# USB_HUB_IC.net
KiCad netlist of a schematic drawn in Altium Designer
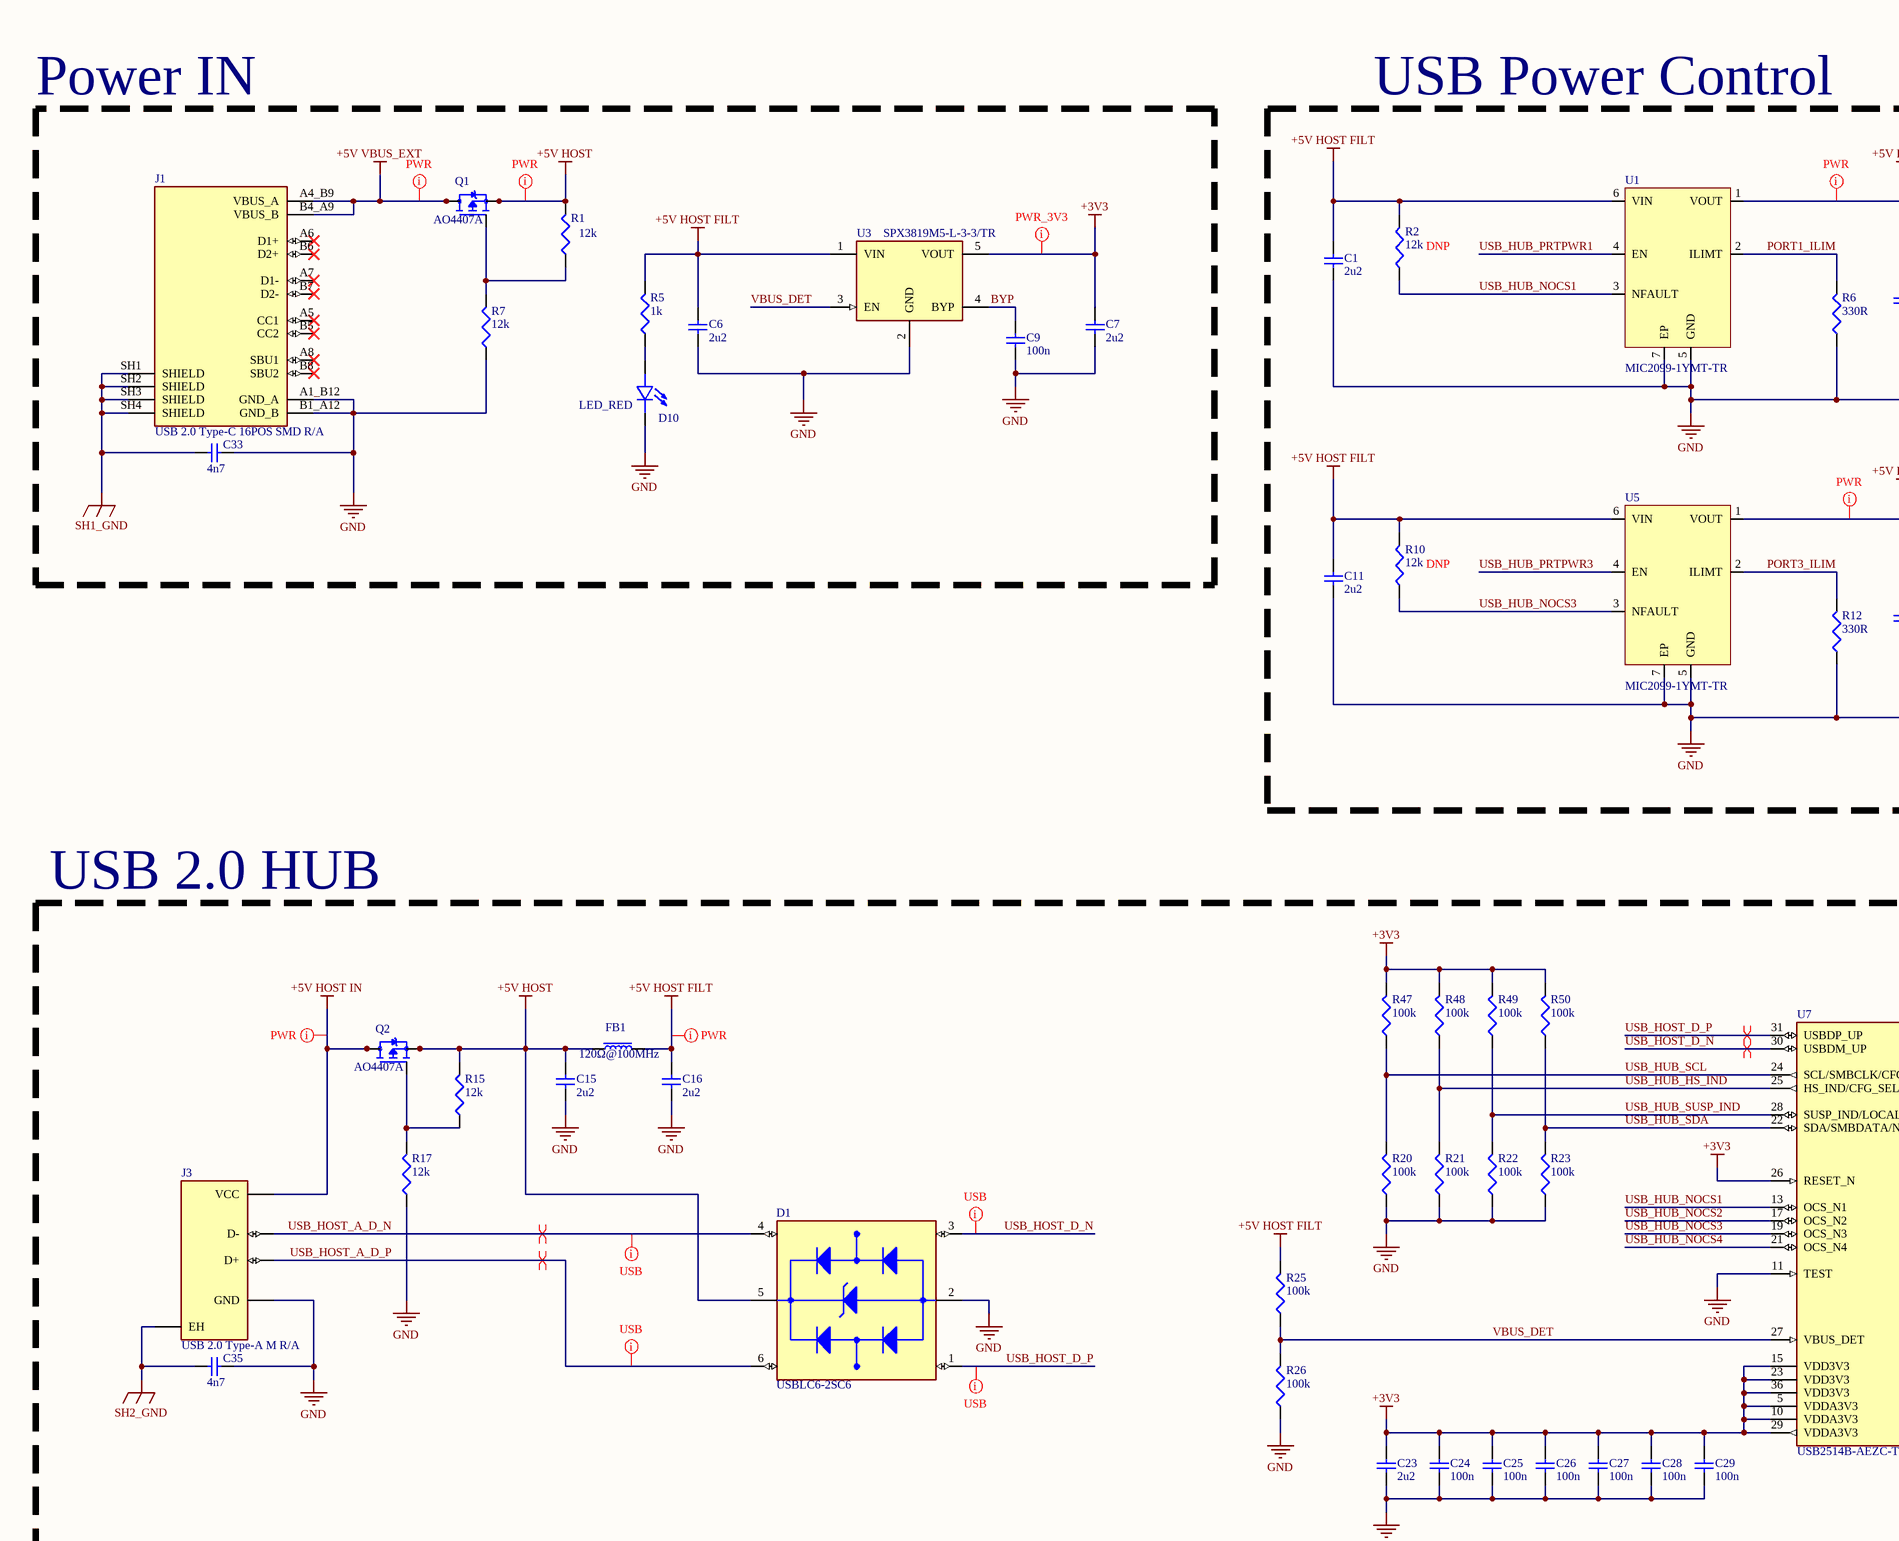
[diagram p0: USB_HUB_IC.SchDoc, top left]
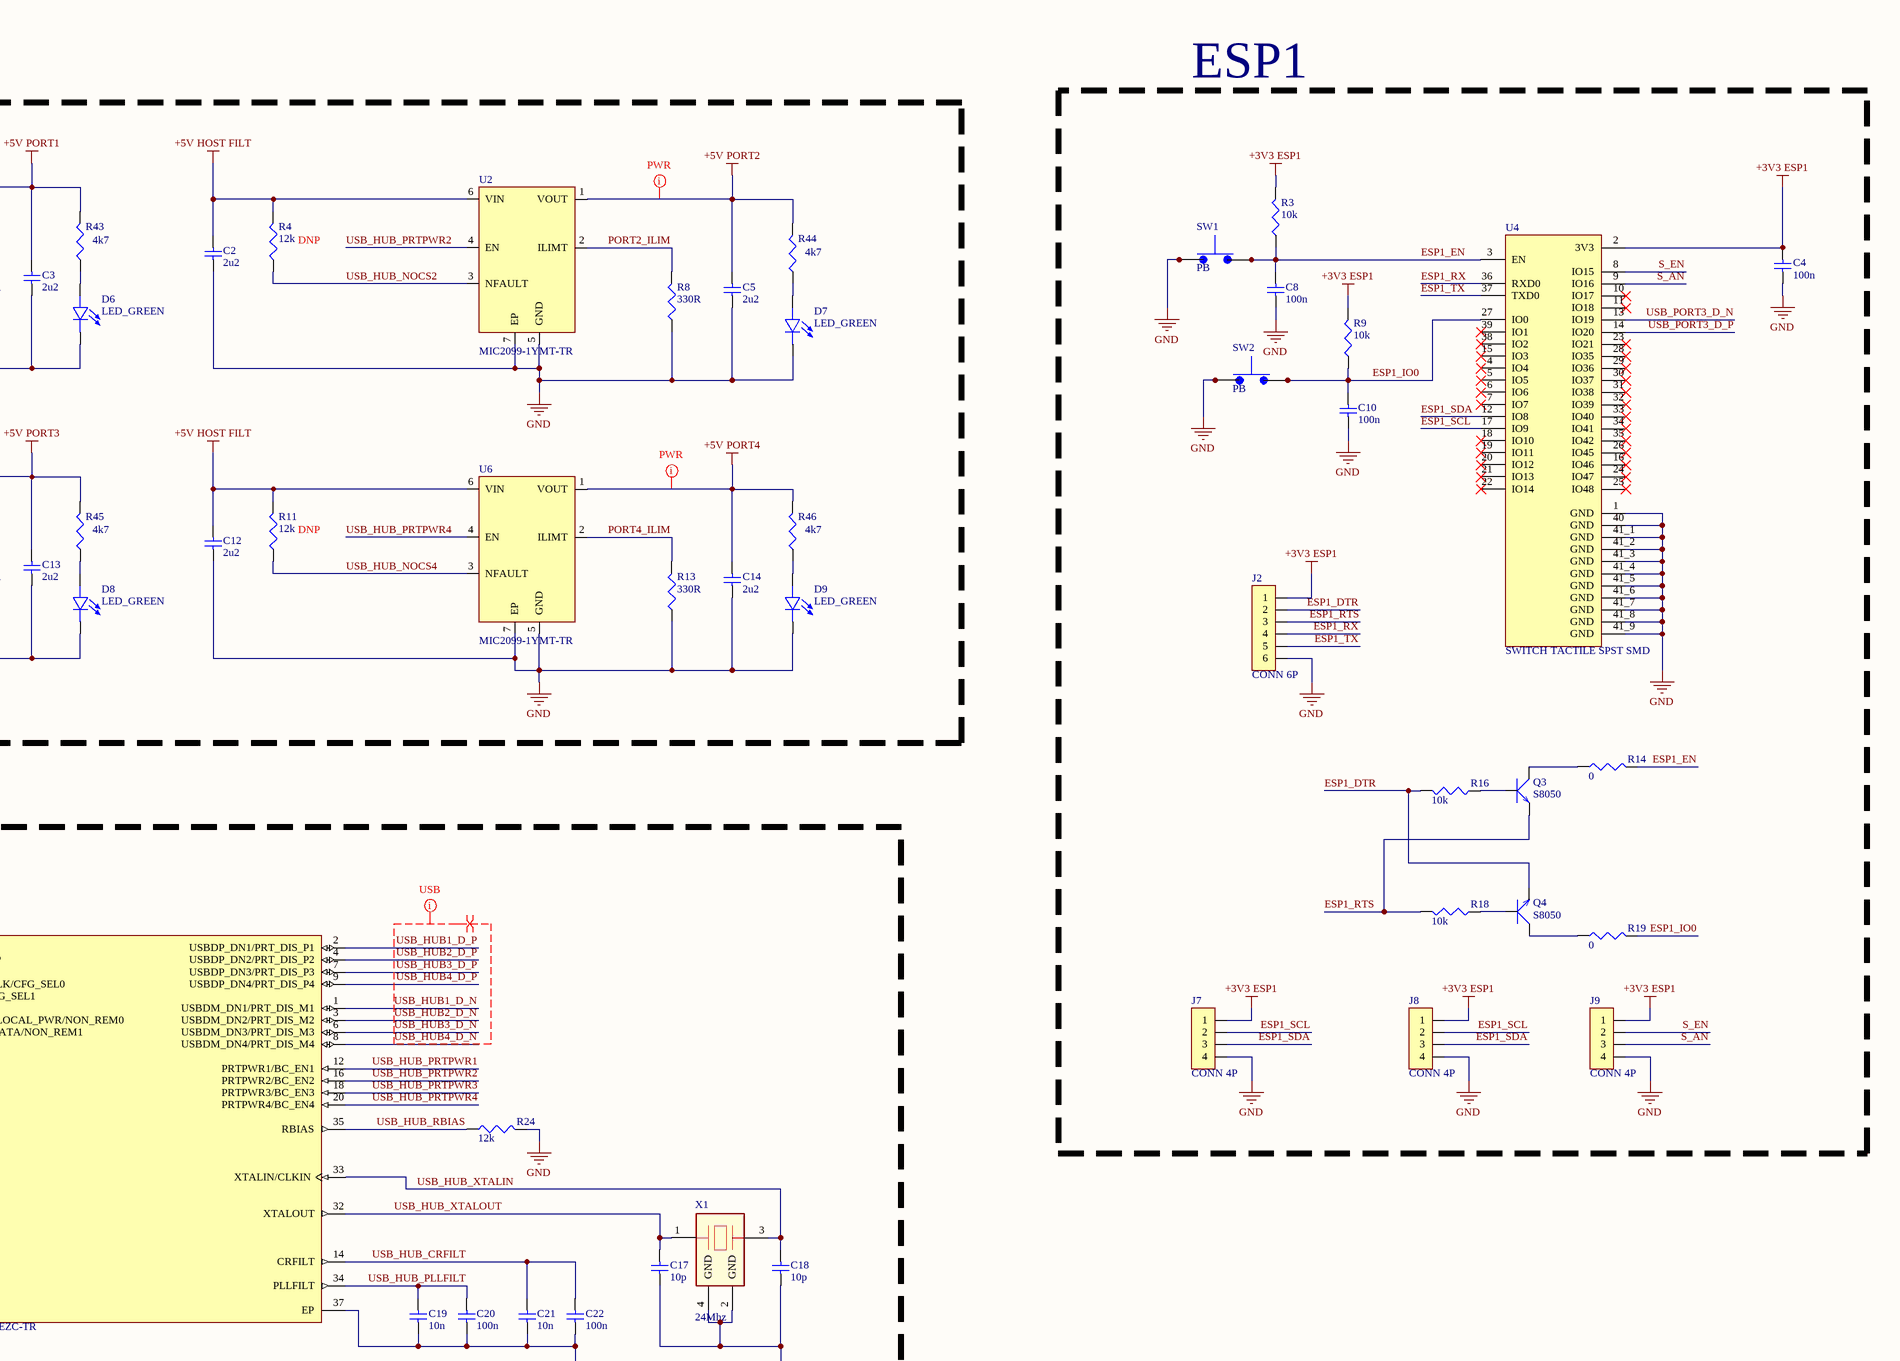
[diagram p1: USB_HUB_IC.SchDoc, top right]
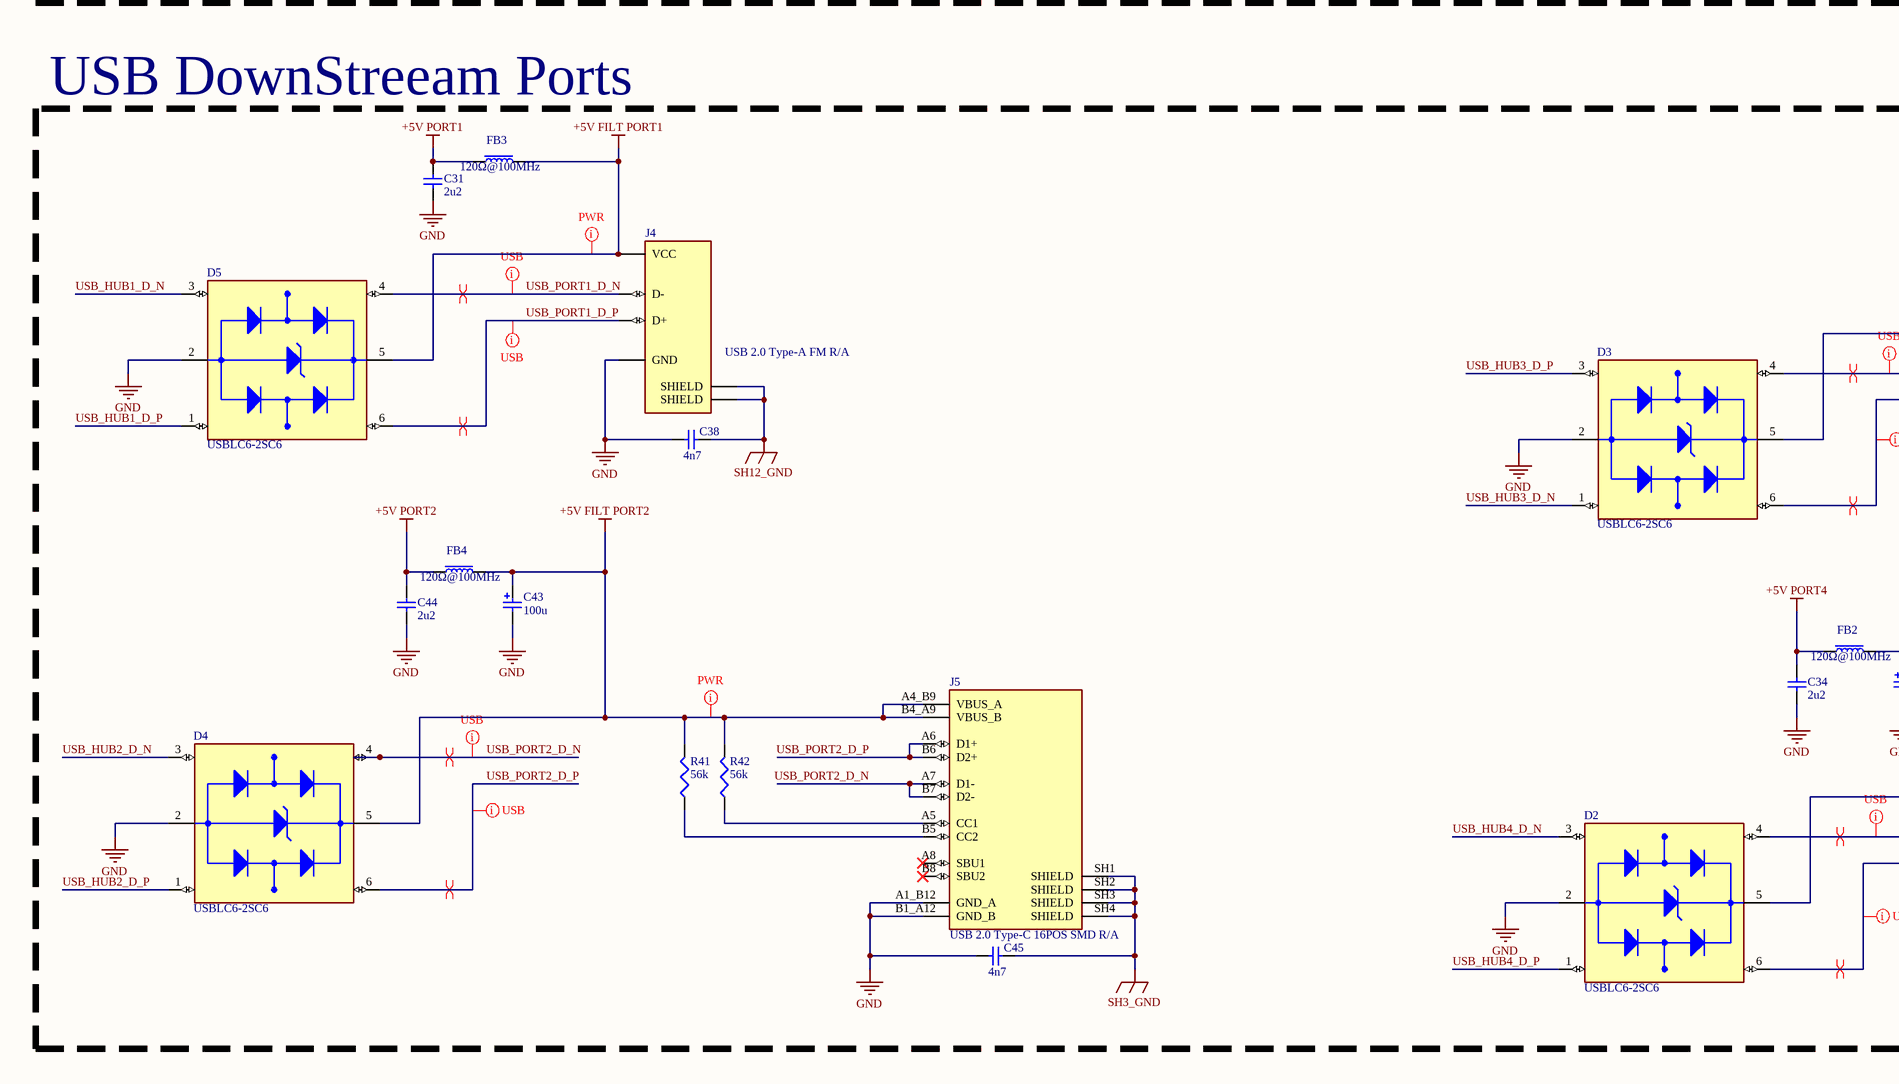
[diagram p2: USB_HUB_IC.SchDoc, bottom left]
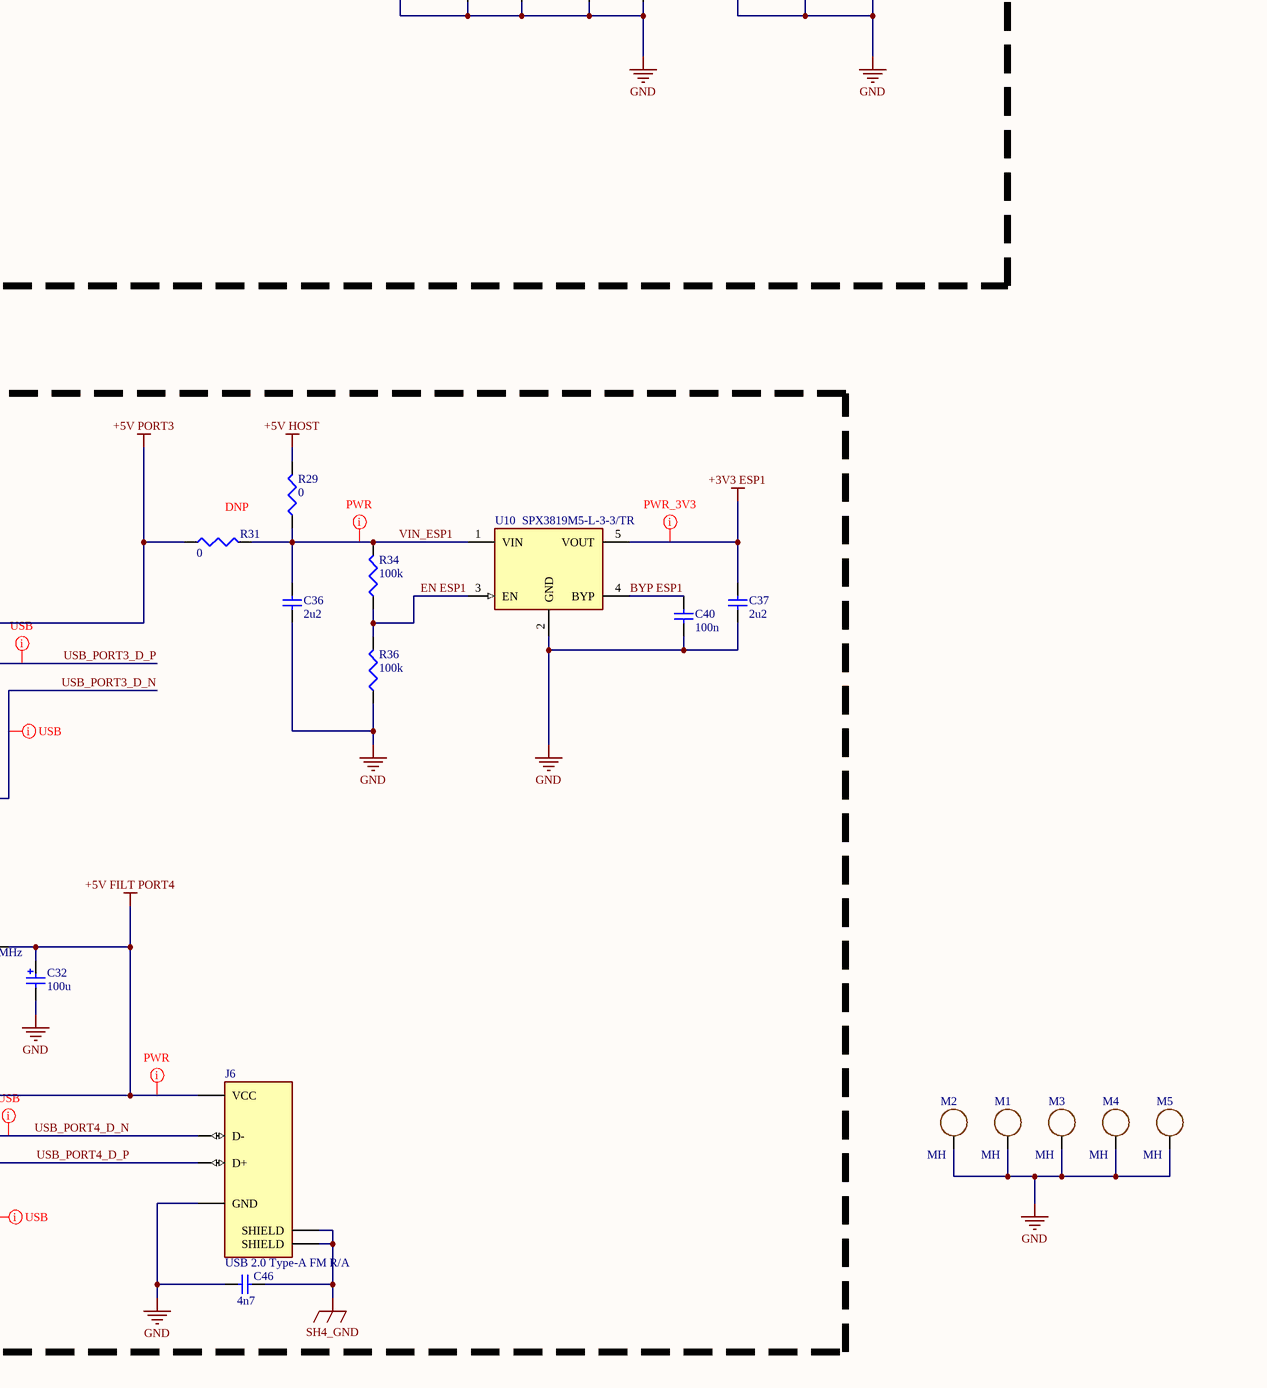
[diagram p3: USB_HUB_IC.SchDoc, bottom right]

(export (version "E")
  (design (tool "Eeschema 10.0.6"))
  (components
    (comp (ref "C1")
      (value "2u2")
      (footprint "CAP_0603")
      (description "CAP CER 2.2uF 16V X7R 0603")
      (fields
        (field (name "MANUFACTURER") "YAGEO")
        (field (name "MANUFACTURER PART NUMBER") "CC0603KRX7R7BB225")
      )
      (libsource (lib "USB2.0_HUB_CAP") (part "YAGEO CC0603KRX7R9BB104_1"))
    )
    (comp (ref "C2")
      (value "2u2")
      (footprint "CAP_0603")
      (description "CAP CER 2.2uF 16V X7R 0603")
      (fields
        (field (name "MANUFACTURER") "YAGEO")
        (field (name "MANUFACTURER PART NUMBER") "CC0603KRX7R7BB225")
      )
      (libsource (lib "USB2.0_HUB_CAP") (part "YAGEO CC0603KRX7R9BB104_1"))
    )
    (comp (ref "C3")
      (value "2u2")
      (footprint "CAP_0603")
      (description "CAP CER 2.2uF 16V X7R 0603")
      (fields
        (field (name "MANUFACTURER") "YAGEO")
        (field (name "MANUFACTURER PART NUMBER") "CC0603KRX7R7BB225")
      )
      (libsource (lib "USB2.0_HUB_CAP") (part "YAGEO CC0603KRX7R9BB104_1"))
    )
    (comp (ref "C4")
      (value "100n")
      (footprint "CAP_0603")
      (description "100nF ±10% 50V Ceramic Capacitor X7R 0603")
      (fields
        (field (name "MANUFACTURER") "YAGEO")
        (field (name "MANUFACTURER PART NUMBER") "CC0603KRX7R9BB104")
      )
      (libsource (lib "USB2.0_HUB_CAP") (part "YAGEO CC0603KRX7R9BB104"))
    )
    (comp (ref "C5")
      (value "2u2")
      (footprint "CAP_0603")
      (description "CAP CER 2.2uF 16V X7R 0603")
      (fields
        (field (name "MANUFACTURER") "YAGEO")
        (field (name "MANUFACTURER PART NUMBER") "CC0603KRX7R7BB225")
      )
      (libsource (lib "USB2.0_HUB_CAP") (part "YAGEO CC0603KRX7R9BB104_1"))
    )
    (comp (ref "C6")
      (value "2u2")
      (footprint "CAP_0603")
      (description "2.2uF ±10% 16V Ceramic Capacitor X7R 0603")
      (fields
        (field (name "MANUFACTURER") "YAGEO")
        (field (name "MANUFACTURER PART NUMBER") "CC0603KRX7R7BB225")
      )
      (libsource (lib "USB2.0_HUB_CAP") (part "YAGEO CC0603KRX7R7BB225"))
    )
    (comp (ref "C7")
      (value "2u2")
      (footprint "CAP_0603")
      (description "2.2uF ±10% 16V Ceramic Capacitor X7R 0603")
      (fields
        (field (name "MANUFACTURER") "YAGEO")
        (field (name "MANUFACTURER PART NUMBER") "CC0603KRX7R7BB225")
      )
      (libsource (lib "USB2.0_HUB_CAP") (part "YAGEO CC0603KRX7R7BB225"))
    )
    (comp (ref "C8")
      (value "100n")
      (footprint "CAP_0603")
      (description "100nF ±10% 50V Ceramic Capacitor X7R 0603")
      (fields
        (field (name "MANUFACTURER") "YAGEO")
        (field (name "MANUFACTURER PART NUMBER") "CC0603KRX7R9BB104")
      )
      (libsource (lib "USB2.0_HUB_CAP") (part "YAGEO CC0603KRX7R9BB104"))
    )
    (comp (ref "C9")
      (value "100n")
      (footprint "CAP_0603")
      (description "100nF ±10% 50V Ceramic Capacitor X7R 0603")
      (fields
        (field (name "MANUFACTURER") "YAGEO")
        (field (name "MANUFACTURER PART NUMBER") "CC0603KRX7R9BB104")
      )
      (libsource (lib "USB2.0_HUB_CAP") (part "YAGEO CC0603KRX7R9BB104"))
    )
    (comp (ref "C10")
      (value "100n")
      (footprint "CAP_0603")
      (description "100nF ±10% 50V Ceramic Capacitor X7R 0603")
      (fields
        (field (name "MANUFACTURER") "YAGEO")
        (field (name "MANUFACTURER PART NUMBER") "CC0603KRX7R9BB104")
      )
      (libsource (lib "USB2.0_HUB_CAP") (part "YAGEO CC0603KRX7R9BB104"))
    )
    (comp (ref "C11")
      (value "2u2")
      (footprint "CAP_0603")
      (description "CAP CER 2.2uF 16V X7R 0603")
      (fields
        (field (name "MANUFACTURER") "YAGEO")
        (field (name "MANUFACTURER PART NUMBER") "CC0603KRX7R7BB225")
      )
      (libsource (lib "USB2.0_HUB_CAP") (part "YAGEO CC0603KRX7R9BB104_1"))
    )
    (comp (ref "C12")
      (value "2u2")
      (footprint "CAP_0603")
      (description "CAP CER 2.2uF 16V X7R 0603")
      (fields
        (field (name "MANUFACTURER") "YAGEO")
        (field (name "MANUFACTURER PART NUMBER") "CC0603KRX7R7BB225")
      )
      (libsource (lib "USB2.0_HUB_CAP") (part "YAGEO CC0603KRX7R9BB104_1"))
    )
    (comp (ref "C13")
      (value "2u2")
      (footprint "CAP_0603")
      (description "CAP CER 2.2uF 16V X7R 0603")
      (fields
        (field (name "MANUFACTURER") "YAGEO")
        (field (name "MANUFACTURER PART NUMBER") "CC0603KRX7R7BB225")
      )
      (libsource (lib "USB2.0_HUB_CAP") (part "YAGEO CC0603KRX7R9BB104_1"))
    )
    (comp (ref "C14")
      (value "2u2")
      (footprint "CAP_0603")
      (description "CAP CER 2.2uF 16V X7R 0603")
      (fields
        (field (name "MANUFACTURER") "YAGEO")
        (field (name "MANUFACTURER PART NUMBER") "CC0603KRX7R7BB225")
      )
      (libsource (lib "USB2.0_HUB_CAP") (part "YAGEO CC0603KRX7R9BB104_1"))
    )
    (comp (ref "C15")
      (value "2u2")
      (footprint "CAP_0603")
      (description "CAP CER 2.2uF 16V X7R 0603")
      (fields
        (field (name "MANUFACTURER") "YAGEO")
        (field (name "MANUFACTURER PART NUMBER") "CC0603KRX7R7BB225")
      )
      (libsource (lib "USB2.0_HUB_CAP") (part "YAGEO CC0603KRX7R9BB104_1"))
    )
    (comp (ref "C16")
      (value "2u2")
      (footprint "CAP_0603")
      (description "CAP CER 2.2uF 16V X7R 0603")
      (fields
        (field (name "MANUFACTURER") "YAGEO")
        (field (name "MANUFACTURER PART NUMBER") "CC0603KRX7R7BB225")
      )
      (libsource (lib "USB2.0_HUB_CAP") (part "YAGEO CC0603KRX7R9BB104_1"))
    )
    (comp (ref "C17")
      (value "10p")
      (footprint "CAP_0603")
      (description "10pF ±1% 50V Ceramic Capacitor NP0 0603")
      (fields
        (field (name "MANUFACTURER") "YAGEO")
        (field (name "MANUFACTURER PART NUMBER") "CC0603FRNPO9BN100")
      )
      (libsource (lib "USB2.0_HUB_CAP") (part "YAGEO CC0603FRNPO9BN100"))
    )
    (comp (ref "C18")
      (value "10p")
      (footprint "CAP_0603")
      (description "10pF ±1% 50V Ceramic Capacitor NP0 0603")
      (fields
        (field (name "MANUFACTURER") "YAGEO")
        (field (name "MANUFACTURER PART NUMBER") "CC0603FRNPO9BN100")
      )
      (libsource (lib "USB2.0_HUB_CAP") (part "YAGEO CC0603FRNPO9BN100"))
    )
    (comp (ref "C19")
      (value "10n")
      (footprint "CAP_0603")
      (description "10nF ±10% 50V Ceramic Capacitor X7R 0603")
      (fields
        (field (name "MANUFACTURER") "YAGEO")
        (field (name "MANUFACTURER PART NUMBER") "CC0603KRX7R9BB103")
      )
      (libsource (lib "USB2.0_HUB_CAP") (part "YAGEO CC0603KRX7R9BB103"))
    )
    (comp (ref "C20")
      (value "100n")
      (footprint "CAP_0603")
      (description "100nF ±10% 50V Ceramic Capacitor X7R 0603")
      (fields
        (field (name "MANUFACTURER") "YAGEO")
        (field (name "MANUFACTURER PART NUMBER") "CC0603KRX7R9BB104")
      )
      (libsource (lib "USB2.0_HUB_CAP") (part "YAGEO CC0603KRX7R9BB104"))
    )
    (comp (ref "C21")
      (value "10n")
      (footprint "CAP_0603")
      (description "10nF ±10% 50V Ceramic Capacitor X7R 0603")
      (fields
        (field (name "MANUFACTURER") "YAGEO")
        (field (name "MANUFACTURER PART NUMBER") "CC0603KRX7R9BB103")
      )
      (libsource (lib "USB2.0_HUB_CAP") (part "YAGEO CC0603KRX7R9BB103"))
    )
    (comp (ref "C22")
      (value "100n")
      (footprint "CAP_0603")
      (description "100nF ±10% 50V Ceramic Capacitor X7R 0603")
      (fields
        (field (name "MANUFACTURER") "YAGEO")
        (field (name "MANUFACTURER PART NUMBER") "CC0603KRX7R9BB104")
      )
      (libsource (lib "USB2.0_HUB_CAP") (part "YAGEO CC0603KRX7R9BB104"))
    )
    (comp (ref "C23")
      (value "2u2")
      (footprint "CAP_0603")
      (description "CAP CER 2.2uF 16V X7R 0603")
      (fields
        (field (name "MANUFACTURER") "YAGEO")
        (field (name "MANUFACTURER PART NUMBER") "CC0603KRX7R7BB225")
      )
      (libsource (lib "USB2.0_HUB_CAP") (part "YAGEO CC0603KRX7R9BB104_1"))
    )
    (comp (ref "C24")
      (value "100n")
      (footprint "CAP_0603")
      (description "100nF ±10% 50V Ceramic Capacitor X7R 0603")
      (fields
        (field (name "MANUFACTURER") "YAGEO")
        (field (name "MANUFACTURER PART NUMBER") "CC0603KRX7R9BB104")
      )
      (libsource (lib "USB2.0_HUB_CAP") (part "YAGEO CC0603KRX7R9BB104"))
    )
    (comp (ref "C25")
      (value "100n")
      (footprint "CAP_0603")
      (description "100nF ±10% 50V Ceramic Capacitor X7R 0603")
      (fields
        (field (name "MANUFACTURER") "YAGEO")
        (field (name "MANUFACTURER PART NUMBER") "CC0603KRX7R9BB104")
      )
      (libsource (lib "USB2.0_HUB_CAP") (part "YAGEO CC0603KRX7R9BB104"))
    )
    (comp (ref "C26")
      (value "100n")
      (footprint "CAP_0603")
      (description "100nF ±10% 50V Ceramic Capacitor X7R 0603")
      (fields
        (field (name "MANUFACTURER") "YAGEO")
        (field (name "MANUFACTURER PART NUMBER") "CC0603KRX7R9BB104")
      )
      (libsource (lib "USB2.0_HUB_CAP") (part "YAGEO CC0603KRX7R9BB104"))
    )
    (comp (ref "C27")
      (value "100n")
      (footprint "CAP_0603")
      (description "100nF ±10% 50V Ceramic Capacitor X7R 0603")
      (fields
        (field (name "MANUFACTURER") "YAGEO")
        (field (name "MANUFACTURER PART NUMBER") "CC0603KRX7R9BB104")
      )
      (libsource (lib "USB2.0_HUB_CAP") (part "YAGEO CC0603KRX7R9BB104"))
    )
    (comp (ref "C28")
      (value "100n")
      (footprint "CAP_0603")
      (description "100nF ±10% 50V Ceramic Capacitor X7R 0603")
      (fields
        (field (name "MANUFACTURER") "YAGEO")
        (field (name "MANUFACTURER PART NUMBER") "CC0603KRX7R9BB104")
      )
      (libsource (lib "USB2.0_HUB_CAP") (part "YAGEO CC0603KRX7R9BB104"))
    )
    (comp (ref "C29")
      (value "100n")
      (footprint "CAP_0603")
      (description "100nF ±10% 50V Ceramic Capacitor X7R 0603")
      (fields
        (field (name "MANUFACTURER") "YAGEO")
        (field (name "MANUFACTURER PART NUMBER") "CC0603KRX7R9BB104")
      )
      (libsource (lib "USB2.0_HUB_CAP") (part "YAGEO CC0603KRX7R9BB104"))
    )
    (comp (ref "C31")
      (value "2u2")
      (footprint "CAP_0603")
      (description "CAP CER 2.2uF 16V X7R 0603")
      (fields
        (field (name "MANUFACTURER") "YAGEO")
        (field (name "MANUFACTURER PART NUMBER") "CC0603KRX7R7BB225")
      )
      (libsource (lib "USB2.0_HUB_CAP") (part "YAGEO CC0603KRX7R9BB104_1"))
    )
    (comp (ref "C32")
      (value "100u")
      (footprint "CAP_SMD")
      (description "100uF ±20% 16V Aluminum Electrolytic Capacitors 2000hrs@105℃")
      (fields
        (field (name "MANUFACTURER") "PANASONIC")
        (field (name "MANUFACTURER PART NUMBER") "EEEFT1C101AR")
      )
      (libsource (lib "USB2.0_HUB_CAP") (part "CAP ALUM 100uF"))
    )
    (comp (ref "C33")
      (value "4n7")
      (footprint "CAP_0603")
      (description "4.7nF ±5% 50V Ceramic Capacitor X7R 0603")
      (fields
        (field (name "MANUFACTURER") "YAGEO")
        (field (name "MANUFACTURER PART NUMBER") "CC0603JRX7R9BB472")
      )
      (libsource (lib "USB2.0_HUB_CAP") (part "YAGEO CC0603JRX7R9BB472"))
    )
    (comp (ref "C34")
      (value "2u2")
      (footprint "CAP_0603")
      (description "CAP CER 2.2uF 16V X7R 0603")
      (fields
        (field (name "MANUFACTURER") "YAGEO")
        (field (name "MANUFACTURER PART NUMBER") "CC0603KRX7R7BB225")
      )
      (libsource (lib "USB2.0_HUB_CAP") (part "YAGEO CC0603KRX7R9BB104_1"))
    )
    (comp (ref "C35")
      (value "4n7")
      (footprint "CAP_0603")
      (description "4.7nF ±5% 50V Ceramic Capacitor X7R 0603")
      (fields
        (field (name "MANUFACTURER") "YAGEO")
        (field (name "MANUFACTURER PART NUMBER") "CC0603JRX7R9BB472")
      )
      (libsource (lib "USB2.0_HUB_CAP") (part "YAGEO CC0603JRX7R9BB472"))
    )
    (comp (ref "C36")
      (value "2u2")
      (footprint "CAP_0603")
      (description "2.2uF ±10% 16V Ceramic Capacitor X7R 0603")
      (fields
        (field (name "MANUFACTURER") "YAGEO")
        (field (name "MANUFACTURER PART NUMBER") "CC0603KRX7R7BB225")
      )
      (libsource (lib "USB2.0_HUB_CAP") (part "YAGEO CC0603KRX7R7BB225"))
    )
    (comp (ref "C37")
      (value "2u2")
      (footprint "CAP_0603")
      (description "2.2uF ±10% 16V Ceramic Capacitor X7R 0603")
      (fields
        (field (name "MANUFACTURER") "YAGEO")
        (field (name "MANUFACTURER PART NUMBER") "CC0603KRX7R7BB225")
      )
      (libsource (lib "USB2.0_HUB_CAP") (part "YAGEO CC0603KRX7R7BB225"))
    )
    (comp (ref "C38")
      (value "4n7")
      (footprint "CAP_0603")
      (description "4.7nF ±5% 50V Ceramic Capacitor X7R 0603")
      (fields
        (field (name "MANUFACTURER") "YAGEO")
        (field (name "MANUFACTURER PART NUMBER") "CC0603JRX7R9BB472")
      )
      (libsource (lib "USB2.0_HUB_CAP") (part "YAGEO CC0603JRX7R9BB472"))
    )
    (comp (ref "C40")
      (value "100n")
      (footprint "CAP_0603")
      (description "100nF ±10% 50V Ceramic Capacitor X7R 0603")
      (fields
        (field (name "MANUFACTURER") "YAGEO")
        (field (name "MANUFACTURER PART NUMBER") "CC0603KRX7R9BB104")
      )
      (libsource (lib "USB2.0_HUB_CAP") (part "YAGEO CC0603KRX7R9BB104"))
    )
    (comp (ref "C43")
      (value "100u")
      (footprint "CAP_SMD")
      (description "100uF ±20% 16V Aluminum Electrolytic Capacitors 2000hrs@105℃")
      (fields
        (field (name "MANUFACTURER") "PANASONIC")
        (field (name "MANUFACTURER PART NUMBER") "EEEFT1C101AR")
      )
      (libsource (lib "USB2.0_HUB_CAP") (part "CAP ALUM 100uF"))
    )
    (comp (ref "C44")
      (value "2u2")
      (footprint "CAP_0603")
      (description "CAP CER 2.2uF 16V X7R 0603")
      (fields
        (field (name "MANUFACTURER") "YAGEO")
        (field (name "MANUFACTURER PART NUMBER") "CC0603KRX7R7BB225")
      )
      (libsource (lib "USB2.0_HUB_CAP") (part "YAGEO CC0603KRX7R9BB104_1"))
    )
    (comp (ref "C45")
      (value "4n7")
      (footprint "CAP_0603")
      (description "4.7nF ±5% 50V Ceramic Capacitor X7R 0603")
      (fields
        (field (name "MANUFACTURER") "YAGEO")
        (field (name "MANUFACTURER PART NUMBER") "CC0603JRX7R9BB472")
      )
      (libsource (lib "USB2.0_HUB_CAP") (part "YAGEO CC0603JRX7R9BB472"))
    )
    (comp (ref "C46")
      (value "4n7")
      (footprint "CAP_0603")
      (description "4.7nF ±5% 50V Ceramic Capacitor X7R 0603")
      (fields
        (field (name "MANUFACTURER") "YAGEO")
        (field (name "MANUFACTURER PART NUMBER") "CC0603JRX7R9BB472")
      )
      (libsource (lib "USB2.0_HUB_CAP") (part "YAGEO CC0603JRX7R9BB472"))
    )
    (comp (ref "D1")
      (value "USBLC6-2SC6")
      (footprint "USBLC6-2SC6_SOT-23-6L")
      (description "17VC Clamp 5A Ipp ESD DIODE SOT-23-6L")
      (fields (field (name "MANUFACTURER") "ST") (field (name "LCSC PART NUMBER") "C7519"))
      (libsource (lib "USB2.0_HUB_Diode") (part "ST USBLC6-2SC6"))
    )
    (comp (ref "D2")
      (value "USBLC6-2SC6")
      (footprint "USBLC6-2SC6_SOT-23-6L")
      (description "17VC Clamp 5A Ipp ESD DIODE SOT-23-6L")
      (fields (field (name "MANUFACTURER") "ST") (field (name "LCSC PART NUMBER") "C7519"))
      (libsource (lib "USB2.0_HUB_Diode") (part "ST USBLC6-2SC6"))
    )
    (comp (ref "D3")
      (value "USBLC6-2SC6")
      (footprint "USBLC6-2SC6_SOT-23-6L")
      (description "17VC Clamp 5A Ipp ESD DIODE SOT-23-6L")
      (fields (field (name "MANUFACTURER") "ST") (field (name "LCSC PART NUMBER") "C7519"))
      (libsource (lib "USB2.0_HUB_Diode") (part "ST USBLC6-2SC6"))
    )
    (comp (ref "D4")
      (value "USBLC6-2SC6")
      (footprint "USBLC6-2SC6_SOT-23-6L")
      (description "17VC Clamp 5A Ipp ESD DIODE SOT-23-6L")
      (fields (field (name "MANUFACTURER") "ST") (field (name "LCSC PART NUMBER") "C7519"))
      (libsource (lib "USB2.0_HUB_Diode") (part "ST USBLC6-2SC6"))
    )
    (comp (ref "D5")
      (value "USBLC6-2SC6")
      (footprint "USBLC6-2SC6_SOT-23-6L")
      (description "17VC Clamp 5A Ipp ESD DIODE SOT-23-6L")
      (fields (field (name "MANUFACTURER") "ST") (field (name "LCSC PART NUMBER") "C7519"))
      (libsource (lib "USB2.0_HUB_Diode") (part "ST USBLC6-2SC6"))
    )
    (comp (ref "D6")
      (value "LED_GREEN")
      (footprint "LED_0805")
      (description "Green 535nm LED Indication - Discrete 2.6V~3.2V 0805")
      (fields
        (field (name "MANUFACTURER") "TONYU")
        (field (name "MANUFACTURER PART NUMBER") "DY-S2012508UGC-T5-3T-03")
      )
      (libsource (lib "USB2.0_HUB_Diode") (part "LED_GREEN"))
    )
    (comp (ref "D7")
      (value "LED_GREEN")
      (footprint "LED_0805")
      (description "Green 535nm LED Indication - Discrete 2.6V~3.2V 0805")
      (fields
        (field (name "MANUFACTURER") "TONYU")
        (field (name "MANUFACTURER PART NUMBER") "DY-S2012508UGC-T5-3T-03")
      )
      (libsource (lib "USB2.0_HUB_Diode") (part "LED_GREEN"))
    )
    (comp (ref "D8")
      (value "LED_GREEN")
      (footprint "LED_0805")
      (description "Green 535nm LED Indication - Discrete 2.6V~3.2V 0805")
      (fields
        (field (name "MANUFACTURER") "TONYU")
        (field (name "MANUFACTURER PART NUMBER") "DY-S2012508UGC-T5-3T-03")
      )
      (libsource (lib "USB2.0_HUB_Diode") (part "LED_GREEN"))
    )
    (comp (ref "D9")
      (value "LED_GREEN")
      (footprint "LED_0805")
      (description "Green 535nm LED Indication - Discrete 2.6V~3.2V 0805")
      (fields
        (field (name "MANUFACTURER") "TONYU")
        (field (name "MANUFACTURER PART NUMBER") "DY-S2012508UGC-T5-3T-03")
      )
      (libsource (lib "USB2.0_HUB_Diode") (part "LED_GREEN"))
    )
    (comp (ref "D10")
      (value "LED_RED")
      (footprint "LED_0805")
      (description "LED RED WATER CLEAR 0805 SMD")
      (fields
        (field (name "MANUFACTURER") "Guiguang light")
        (field (name "MANUFACTURER PART NUMBER") "GL0805UR01")
      )
      (libsource (lib "USB2.0_HUB_Diode") (part "LED_RED"))
    )
    (comp (ref "FB1")
      (value "120Ω@100MHz")
      (footprint "FB_0805")
      (description "FERRITE BEAD 120Ω 0805 1LN")
      (fields
        (field (name "MANUFACTURER") "muRata")
        (field (name "MANUFACTURER PART NUMBER") "BLM21PG121SN1D")
      )
      (libsource (lib "USB2.0_HUB_FB") (part "muRata BLM21PG121SN1D"))
    )
    (comp (ref "FB2")
      (value "120Ω@100MHz")
      (footprint "FB_0805")
      (description "FERRITE BEAD 120Ω 0805 1LN")
      (fields
        (field (name "MANUFACTURER") "muRata")
        (field (name "MANUFACTURER PART NUMBER") "BLM21PG121SN1D")
      )
      (libsource (lib "USB2.0_HUB_FB") (part "muRata BLM21PG121SN1D"))
    )
    (comp (ref "FB3")
      (value "120Ω@100MHz")
      (footprint "FB_0805")
      (description "FERRITE BEAD 120Ω 0805 1LN")
      (fields
        (field (name "MANUFACTURER") "muRata")
        (field (name "MANUFACTURER PART NUMBER") "BLM21PG121SN1D")
      )
      (libsource (lib "USB2.0_HUB_FB") (part "muRata BLM21PG121SN1D"))
    )
    (comp (ref "FB4")
      (value "120Ω@100MHz")
      (footprint "FB_0805")
      (description "FERRITE BEAD 120Ω 0805 1LN")
      (fields
        (field (name "MANUFACTURER") "muRata")
        (field (name "MANUFACTURER PART NUMBER") "BLM21PG121SN1D")
      )
      (libsource (lib "USB2.0_HUB_FB") (part "muRata BLM21PG121SN1D"))
    )
    (comp (ref "J1")
      (value "USB 2.0 Type-C 16POS SMD R/A")
      (footprint "GT-USB-7010B")
      (description "USB-C (USB TYPE-C) Receptacle Connector 16 Position Surface Mount, Right Angle")
      (fields
        (field (name "MANUFACTURER") "G-Switch")
        (field (name "MANUFACTURER PART NUMBER") "GT-USB-7010ASV")
      )
      (libsource (lib "USB2.0_HUB_CONN") (part "GT-USB-7010B"))
    )
    (comp (ref "J2")
      (value "CONN 6P")
      (footprint "JST_6P_GH_W/A")
      (description "Connector Header 6 position 1.25mm Pitch 1A Surface Mount, Right Angle -25℃~+85℃")
      (fields
        (field (name "MANUFACTURER") "SHOU HAN")
        (field (name "MANUFACTURER PART NUMBER") "1.25-6PWTDK")
      )
      (libsource (lib "USB2.0_HUB_CONN") (part "JST_6P_GH_R/A"))
    )
    (comp (ref "J3")
      (value "USB 2.0 Type-A M R/A")
      (footprint "Male USB 2.0 Type-A 4POS SMD R/A")
      (description "USB-A (USB TYPE-A) Receptacle Connector 4 Position Surface Mount, Right Angle")
      (fields (field (name "MANUFACTURER") "XUNPU") (field (name "MANUFACTURER PART NUMBER") "USB-212-BCW"))
      (libsource (lib "USB2.0_HUB_CONN") (part "USB 2.0 Type-A M R/A"))
    )
    (comp (ref "J4")
      (value "USB 2.0 Type-A FM R/A")
      (footprint "Femalem USB 2.0 Type-A 4POS SMD R/A")
      (description "USB-A (USB TYPE-A) Receptacle Connector 4 Position Surface Mount, Right Angle")
      (fields
        (field (name "MANUFACTURER") "SHOU HAN")
        (field (name "MANUFACTURER PART NUMBER") "10.0 QHHTZB6.3")
      )
      (libsource (lib "USB2.0_HUB_CONN") (part "USB 2.0 Type-A FM R/A"))
    )
    (comp (ref "J5")
      (value "USB 2.0 Type-C 16POS SMD R/A")
      (footprint "GT-USB-7010B")
      (description "USB-C (USB TYPE-C) Receptacle Connector 16 Position Surface Mount, Right Angle")
      (fields
        (field (name "MANUFACTURER") "G-Switch")
        (field (name "MANUFACTURER PART NUMBER") "GT-USB-7010ASV")
      )
      (libsource (lib "") (part "GT-USB-7010B_1"))
    )
    (comp (ref "J6")
      (value "USB 2.0 Type-A FM R/A")
      (footprint "Femalem USB 2.0 Type-A 4POS SMD R/A")
      (description "USB-A (USB TYPE-A) Receptacle Connector 4 Position Surface Mount, Right Angle")
      (fields
        (field (name "MANUFACTURER") "SHOU HAN")
        (field (name "MANUFACTURER PART NUMBER") "10.0 QHHTZB6.3")
      )
      (libsource (lib "USB2.0_HUB_CONN") (part "USB 2.0 Type-A FM R/A"))
    )
    (comp (ref "J7")
      (value "CONN 4P")
      (footprint "JST_4P_GH_R/A")
      (description "Connector Header 4 position 1.25mm Pitch 1A Surface Mount, Right Angle -25℃~+85℃")
      (fields
        (field (name "MANUFACTURER") "XUNPU")
        (field (name "MANUFACTURER PART NUMBER") "WAFER-GH1.25-4PWB")
      )
      (libsource (lib "USB2.0_HUB_CONN") (part "JST_4P_GH_R/A"))
    )
    (comp (ref "J8")
      (value "CONN 4P")
      (footprint "JST_4P_GH_R/A")
      (description "Connector Header 4 position 1.25mm Pitch 1A Surface Mount, Right Angle -25℃~+85℃")
      (fields
        (field (name "MANUFACTURER") "XUNPU")
        (field (name "MANUFACTURER PART NUMBER") "WAFER-GH1.25-4PWB")
      )
      (libsource (lib "USB2.0_HUB_CONN") (part "JST_4P_GH_R/A"))
    )
    (comp (ref "J9")
      (value "CONN 4P")
      (footprint "JST_4P_GH_R/A")
      (description "Connector Header 4 position 1.25mm Pitch 1A Surface Mount, Right Angle -25℃~+85℃")
      (fields
        (field (name "MANUFACTURER") "XUNPU")
        (field (name "MANUFACTURER PART NUMBER") "WAFER-GH1.25-4PWB")
      )
      (libsource (lib "USB2.0_HUB_CONN") (part "JST_4P_GH_R/A"))
    )
    (comp (ref "M1")
      (value "MH")
      (footprint "M2_Mounting_Hole")
      (libsource (lib "USB2.0_HUB") (part "M2_Mounting_hole"))
    )
    (comp (ref "M2")
      (value "MH")
      (footprint "M2_Mounting_Hole")
      (libsource (lib "USB2.0_HUB") (part "M2_Mounting_hole"))
    )
    (comp (ref "M3")
      (value "MH")
      (footprint "M2_Mounting_Hole")
      (libsource (lib "USB2.0_HUB") (part "M2_Mounting_hole"))
    )
    (comp (ref "M4")
      (value "MH")
      (footprint "M2_Mounting_Hole")
      (libsource (lib "USB2.0_HUB") (part "M2_Mounting_hole"))
    )
    (comp (ref "M5")
      (value "MH")
      (footprint "M2_Mounting_Hole")
      (libsource (lib "USB2.0_HUB") (part "M2_Mounting_hole"))
    )
    (comp (ref "Q1")
      (value "AO4407A")
      (footprint "AO4407A_SOIC-8")
      (description "P-Channel 30V 12A 3.1W Surface Mount SOIC-8")
      (fields (field (name "MANUFACTURER") "AOS") (field (name "LCSC PART NUMBER") "C16072"))
      (libsource (lib "USB2.0_HUB") (part "AOS AO4407A"))
    )
    (comp (ref "Q2")
      (value "AO4407A")
      (footprint "AO4407A_SOIC-8")
      (description "P-Channel 30V 12A 3.1W Surface Mount SOIC-8")
      (fields (field (name "MANUFACTURER") "AOS") (field (name "LCSC PART NUMBER") "C16072"))
      (libsource (lib "USB2.0_HUB") (part "AOS AO4407A"))
    )
    (comp (ref "Q3")
      (value "S8050")
      (footprint "S8050_SOT-23")
      (description "Bipolar (BJT) Transistor 25V 500mA 150MHz 300mW Surface Mount SOT-23")
      (fields (field (name "MANUFACTURER") "JSMSEMI") (field (name "LCSC PART NUMBER") "C916390"))
      (libsource (lib "USB2.0_HUB") (part "JSMSEMI S8050"))
    )
    (comp (ref "Q4")
      (value "S8050")
      (footprint "S8050_SOT-23")
      (description "Bipolar (BJT) Transistor 25V 500mA 150MHz 300mW Surface Mount SOT-23")
      (fields (field (name "MANUFACTURER") "JSMSEMI") (field (name "LCSC PART NUMBER") "C916390"))
      (libsource (lib "USB2.0_HUB") (part "JSMSEMI S8050"))
    )
    (comp (ref "R1")
      (value "12k")
      (footprint "RES_0603")
      (description "RES 12kΩ ±1% 100mW 0603")
      (fields
        (field (name "MANUFACTURER") "YAGEO")
        (field (name "MANUFACTURER PART NUMBER") "RC0603FR-0712KL")
      )
      (libsource (lib "USB2.0_HUB_RES") (part "YAGEO RC0603FR-0712KL"))
    )
    (comp (ref "R2")
      (value "12k")
      (footprint "RES_0603")
      (description "RES 12kΩ ±1% 100mW 0603")
      (fields
        (field (name "MANUFACTURER") "YAGEO")
        (field (name "MANUFACTURER PART NUMBER") "RC0603FR-0712KL")
      )
      (libsource (lib "USB2.0_HUB_RES") (part "YAGEO RC0603FR-0712KL"))
    )
    (comp (ref "R3")
      (value "10k")
      (footprint "RES_0603")
      (description "100mW 10kΩ 75V Thick Film Resistor ±100ppm/℃ ±1% 0603 Chip Resistor - Surface Mount RoHS")
      (fields
        (field (name "MANUFACTURER") "YAGEO")
        (field (name "MANUFACTURER PART NUMBER") "RC0603FR-0710KL")
      )
      (libsource (lib "USB2.0_HUB_RES") (part "YAGEO RC0603FR-0710KL"))
    )
    (comp (ref "R4")
      (value "12k")
      (footprint "RES_0603")
      (description "RES 12kΩ ±1% 100mW 0603")
      (fields
        (field (name "MANUFACTURER") "YAGEO")
        (field (name "MANUFACTURER PART NUMBER") "RC0603FR-0712KL")
      )
      (libsource (lib "USB2.0_HUB_RES") (part "YAGEO RC0603FR-0712KL"))
    )
    (comp (ref "R5")
      (value "1k")
      (footprint "RES_0603")
      (description "100mW 1kΩ 75V Thick Film Resistor ±100ppm/℃ ±5% 0603 Chip Resistor - Surface Mount RoHS")
      (fields
        (field (name "MANUFACTURER") "YAGEO")
        (field (name "MANUFACTURER PART NUMBER") "RC0603JR-071KL")
      )
      (libsource (lib "USB2.0_HUB_RES") (part "YAGEO RC0603JR-071KL"))
    )
    (comp (ref "R6")
      (value "330R")
      (footprint "RES_0603")
      (description "RES 330Ω ±5% 100mW 0603")
      (fields
        (field (name "MANUFACTURER") "YAGEO")
        (field (name "MANUFACTURER PART NUMBER") "RC0603JR-07330RL")
      )
      (libsource (lib "USB2.0_HUB_RES") (part "YAGEO RC0603JR-07330RL"))
    )
    (comp (ref "R7")
      (value "12k")
      (footprint "RES_0603")
      (description "RES 12kΩ ±1% 100mW 0603")
      (fields
        (field (name "MANUFACTURER") "YAGEO")
        (field (name "MANUFACTURER PART NUMBER") "RC0603FR-0712KL")
      )
      (libsource (lib "USB2.0_HUB_RES") (part "YAGEO RC0603FR-0712KL"))
    )
    (comp (ref "R8")
      (value "330R")
      (footprint "RES_0603")
      (description "RES 330Ω ±5% 100mW 0603")
      (fields
        (field (name "MANUFACTURER") "YAGEO")
        (field (name "MANUFACTURER PART NUMBER") "RC0603JR-07330RL")
      )
      (libsource (lib "USB2.0_HUB_RES") (part "YAGEO RC0603JR-07330RL"))
    )
    (comp (ref "R9")
      (value "10k")
      (footprint "RES_0603")
      (description "100mW 10kΩ 75V Thick Film Resistor ±100ppm/℃ ±1% 0603 Chip Resistor - Surface Mount RoHS")
      (fields
        (field (name "MANUFACTURER") "YAGEO")
        (field (name "MANUFACTURER PART NUMBER") "RC0603FR-0710KL")
      )
      (libsource (lib "USB2.0_HUB_RES") (part "YAGEO RC0603FR-0710KL"))
    )
    (comp (ref "R10")
      (value "12k")
      (footprint "RES_0603")
      (description "RES 12kΩ ±1% 100mW 0603")
      (fields
        (field (name "MANUFACTURER") "YAGEO")
        (field (name "MANUFACTURER PART NUMBER") "RC0603FR-0712KL")
      )
      (libsource (lib "USB2.0_HUB_RES") (part "YAGEO RC0603FR-0712KL"))
    )
    (comp (ref "R11")
      (value "12k")
      (footprint "RES_0603")
      (description "RES 12kΩ ±1% 100mW 0603")
      (fields
        (field (name "MANUFACTURER") "YAGEO")
        (field (name "MANUFACTURER PART NUMBER") "RC0603FR-0712KL")
      )
      (libsource (lib "USB2.0_HUB_RES") (part "YAGEO RC0603FR-0712KL"))
    )
    (comp (ref "R12")
      (value "330R")
      (footprint "RES_0603")
      (description "RES 330Ω ±5% 100mW 0603")
      (fields
        (field (name "MANUFACTURER") "YAGEO")
        (field (name "MANUFACTURER PART NUMBER") "RC0603JR-07330RL")
      )
      (libsource (lib "USB2.0_HUB_RES") (part "YAGEO RC0603JR-07330RL"))
    )
    (comp (ref "R13")
      (value "330R")
      (footprint "RES_0603")
      (description "RES 330Ω ±5% 100mW 0603")
      (fields
        (field (name "MANUFACTURER") "YAGEO")
        (field (name "MANUFACTURER PART NUMBER") "RC0603JR-07330RL")
      )
      (libsource (lib "USB2.0_HUB_RES") (part "YAGEO RC0603JR-07330RL"))
    )
    (comp (ref "R14")
      (value "0")
      (footprint "RES_0603")
      (description "100mW 0Ω 75V Thick Film Resistor ±5% 0603 Chip Resistor - Surface Mount RoHS")
      (fields
        (field (name "MANUFACTURER") "YAGEO")
        (field (name "MANUFACTURER PART NUMBER") "RC0603JR-070RL")
      )
      (libsource (lib "USB2.0_HUB_RES") (part "YAGEO RC0603JR-070RL"))
    )
    (comp (ref "R15")
      (value "12k")
      (footprint "RES_0603")
      (description "RES 12kΩ ±1% 100mW 0603")
      (fields
        (field (name "MANUFACTURER") "YAGEO")
        (field (name "MANUFACTURER PART NUMBER") "RC0603FR-0712KL")
      )
      (libsource (lib "USB2.0_HUB_RES") (part "YAGEO RC0603FR-0712KL"))
    )
    (comp (ref "R16")
      (value "10k")
      (footprint "RES_0603")
      (description "100mW 10kΩ 75V Thick Film Resistor ±100ppm/℃ ±1% 0603 Chip Resistor - Surface Mount RoHS")
      (fields
        (field (name "MANUFACTURER") "YAGEO")
        (field (name "MANUFACTURER PART NUMBER") "RC0603FR-0710KL")
      )
      (libsource (lib "USB2.0_HUB_RES") (part "YAGEO RC0603FR-0710KL"))
    )
    (comp (ref "R17")
      (value "12k")
      (footprint "RES_0603")
      (description "RES 12kΩ ±1% 100mW 0603")
      (fields
        (field (name "MANUFACTURER") "YAGEO")
        (field (name "MANUFACTURER PART NUMBER") "RC0603FR-0712KL")
      )
      (libsource (lib "USB2.0_HUB_RES") (part "YAGEO RC0603FR-0712KL"))
    )
    (comp (ref "R18")
      (value "10k")
      (footprint "RES_0603")
      (description "100mW 10kΩ 75V Thick Film Resistor ±100ppm/℃ ±1% 0603 Chip Resistor - Surface Mount RoHS")
      (fields
        (field (name "MANUFACTURER") "YAGEO")
        (field (name "MANUFACTURER PART NUMBER") "RC0603FR-0710KL")
      )
      (libsource (lib "USB2.0_HUB_RES") (part "YAGEO RC0603FR-0710KL"))
    )
    (comp (ref "R19")
      (value "0")
      (footprint "RES_0603")
      (description "100mW 0Ω 75V Thick Film Resistor ±5% 0603 Chip Resistor - Surface Mount RoHS")
      (fields
        (field (name "MANUFACTURER") "YAGEO")
        (field (name "MANUFACTURER PART NUMBER") "RC0603JR-070RL")
      )
      (libsource (lib "USB2.0_HUB_RES") (part "YAGEO RC0603JR-070RL"))
    )
    (comp (ref "R20")
      (value "100k")
      (footprint "RES_0603")
      (description "RES 100kΩ ±5% 100mW 0603")
      (fields
        (field (name "MANUFACTURER") "YAGEO")
        (field (name "MANUFACTURER PART NUMBER") "RC0603JR-07100KL")
      )
      (libsource (lib "USB2.0_HUB_RES") (part "YAGEO RC0603JR-07100KL"))
    )
    (comp (ref "R21")
      (value "100k")
      (footprint "RES_0603")
      (description "RES 100kΩ ±5% 100mW 0603")
      (fields
        (field (name "MANUFACTURER") "YAGEO")
        (field (name "MANUFACTURER PART NUMBER") "RC0603JR-07100KL")
      )
      (libsource (lib "USB2.0_HUB_RES") (part "YAGEO RC0603JR-07100KL"))
    )
    (comp (ref "R22")
      (value "100k")
      (footprint "RES_0603")
      (description "RES 100kΩ ±5% 100mW 0603")
      (fields
        (field (name "MANUFACTURER") "YAGEO")
        (field (name "MANUFACTURER PART NUMBER") "RC0603JR-07100KL")
      )
      (libsource (lib "USB2.0_HUB_RES") (part "YAGEO RC0603JR-07100KL"))
    )
    (comp (ref "R23")
      (value "100k")
      (footprint "RES_0603")
      (description "RES 100kΩ ±5% 100mW 0603")
      (fields
        (field (name "MANUFACTURER") "YAGEO")
        (field (name "MANUFACTURER PART NUMBER") "RC0603JR-07100KL")
      )
      (libsource (lib "USB2.0_HUB_RES") (part "YAGEO RC0603JR-07100KL"))
    )
    (comp (ref "R24")
      (value "12k")
      (footprint "RES_0603")
      (description "RES 12kΩ ±1% 100mW 0603")
      (fields
        (field (name "MANUFACTURER") "YAGEO")
        (field (name "MANUFACTURER PART NUMBER") "RC0603FR-0712KL")
      )
      (libsource (lib "USB2.0_HUB_RES") (part "YAGEO RC0603FR-0712KL"))
    )
    (comp (ref "R25")
      (value "100k")
      (footprint "RES_0603")
      (description "RES 100kΩ ±5% 100mW 0603")
      (fields
        (field (name "MANUFACTURER") "YAGEO")
        (field (name "MANUFACTURER PART NUMBER") "RC0603JR-07100KL")
      )
      (libsource (lib "USB2.0_HUB_RES") (part "YAGEO RC0603JR-07100KL"))
    )
    (comp (ref "R26")
      (value "100k")
      (footprint "RES_0603")
      (description "RES 100kΩ ±5% 100mW 0603")
      (fields
        (field (name "MANUFACTURER") "YAGEO")
        (field (name "MANUFACTURER PART NUMBER") "RC0603JR-07100KL")
      )
      (libsource (lib "USB2.0_HUB_RES") (part "YAGEO RC0603JR-07100KL"))
    )
    (comp (ref "R29")
      (value "0")
      (footprint "RES_0603")
      (description "100mW 0Ω 75V Thick Film Resistor ±5% 0603 Chip Resistor - Surface Mount RoHS")
      (fields
        (field (name "MANUFACTURER") "YAGEO")
        (field (name "MANUFACTURER PART NUMBER") "RC0603JR-070RL")
      )
      (libsource (lib "USB2.0_HUB_RES") (part "YAGEO RC0603JR-070RL"))
    )
    (comp (ref "R31")
      (value "0")
      (footprint "RES_0603")
      (description "100mW 0Ω 75V Thick Film Resistor ±5% 0603 Chip Resistor - Surface Mount RoHS")
      (fields
        (field (name "MANUFACTURER") "YAGEO")
        (field (name "MANUFACTURER PART NUMBER") "RC0603JR-070RL")
      )
      (libsource (lib "USB2.0_HUB_RES") (part "YAGEO RC0603JR-070RL"))
    )
    (comp (ref "R34")
      (value "100k")
      (footprint "RES_0603")
      (description "RES 100kΩ ±5% 100mW 0603")
      (fields
        (field (name "MANUFACTURER") "YAGEO")
        (field (name "MANUFACTURER PART NUMBER") "RC0603JR-07100KL")
      )
      (libsource (lib "USB2.0_HUB_RES") (part "YAGEO RC0603JR-07100KL"))
    )
    (comp (ref "R36")
      (value "100k")
      (footprint "RES_0603")
      (description "RES 100kΩ ±5% 100mW 0603")
      (fields
        (field (name "MANUFACTURER") "YAGEO")
        (field (name "MANUFACTURER PART NUMBER") "RC0603JR-07100KL")
      )
      (libsource (lib "USB2.0_HUB_RES") (part "YAGEO RC0603JR-07100KL"))
    )
    (comp (ref "R41")
      (value "56k")
      (footprint "RES_0603")
      (description "100mW 56kΩ 75V Thick Film Resistor ±100ppm/℃ ±1% 0603 Chip Resistor - Surface Mount RoHS")
      (fields
        (field (name "MANUFACTURER") "YAGEO")
        (field (name "MANUFACTURER PART NUMBER") "RC0603FR-0756KL")
      )
      (libsource (lib "USB2.0_HUB_RES") (part "YAGEO RC0603FR-0756KL"))
    )
    (comp (ref "R42")
      (value "56k")
      (footprint "RES_0603")
      (description "100mW 56kΩ 75V Thick Film Resistor ±100ppm/℃ ±1% 0603 Chip Resistor - Surface Mount RoHS")
      (fields
        (field (name "MANUFACTURER") "YAGEO")
        (field (name "MANUFACTURER PART NUMBER") "RC0603FR-0756KL")
      )
      (libsource (lib "USB2.0_HUB_RES") (part "YAGEO RC0603FR-0756KL"))
    )
    (comp (ref "R43")
      (value "4k7")
      (footprint "RES_0603")
      (description "100mW 4.7kΩ 75V Thick Film Resistor ±100ppm/℃ ±5% 0603 Chip Resistor - Surface Mount RoHS")
      (fields
        (field (name "MANUFACTURER") "YAGEO")
        (field (name "MANUFACTURER PART NUMBER") "RC0603JR-074K7L")
      )
      (libsource (lib "USB2.0_HUB_RES") (part "YAGEO RC0603JR-074K7L"))
    )
    (comp (ref "R44")
      (value "4k7")
      (footprint "RES_0603")
      (description "100mW 4.7kΩ 75V Thick Film Resistor ±100ppm/℃ ±5% 0603 Chip Resistor - Surface Mount RoHS")
      (fields
        (field (name "MANUFACTURER") "YAGEO")
        (field (name "MANUFACTURER PART NUMBER") "RC0603JR-074K7L")
      )
      (libsource (lib "USB2.0_HUB_RES") (part "YAGEO RC0603JR-074K7L"))
    )
    (comp (ref "R45")
      (value "4k7")
      (footprint "RES_0603")
      (description "100mW 4.7kΩ 75V Thick Film Resistor ±100ppm/℃ ±5% 0603 Chip Resistor - Surface Mount RoHS")
      (fields
        (field (name "MANUFACTURER") "YAGEO")
        (field (name "MANUFACTURER PART NUMBER") "RC0603JR-074K7L")
      )
      (libsource (lib "USB2.0_HUB_RES") (part "YAGEO RC0603JR-074K7L"))
    )
    (comp (ref "R46")
      (value "4k7")
      (footprint "RES_0603")
      (description "100mW 4.7kΩ 75V Thick Film Resistor ±100ppm/℃ ±5% 0603 Chip Resistor - Surface Mount RoHS")
      (fields
        (field (name "MANUFACTURER") "YAGEO")
        (field (name "MANUFACTURER PART NUMBER") "RC0603JR-074K7L")
      )
      (libsource (lib "USB2.0_HUB_RES") (part "YAGEO RC0603JR-074K7L"))
    )
    (comp (ref "R47")
      (value "100k")
      (footprint "RES_0603")
      (description "RES 100kΩ ±5% 100mW 0603")
      (fields
        (field (name "MANUFACTURER") "YAGEO")
        (field (name "MANUFACTURER PART NUMBER") "RC0603JR-07100KL")
      )
      (libsource (lib "USB2.0_HUB_RES") (part "YAGEO RC0603JR-07100KL"))
    )
    (comp (ref "R48")
      (value "100k")
      (footprint "RES_0603")
      (description "RES 100kΩ ±5% 100mW 0603")
      (fields
        (field (name "MANUFACTURER") "YAGEO")
        (field (name "MANUFACTURER PART NUMBER") "RC0603JR-07100KL")
      )
      (libsource (lib "USB2.0_HUB_RES") (part "YAGEO RC0603JR-07100KL"))
    )
    (comp (ref "R49")
      (value "100k")
      (footprint "RES_0603")
      (description "RES 100kΩ ±5% 100mW 0603")
      (fields
        (field (name "MANUFACTURER") "YAGEO")
        (field (name "MANUFACTURER PART NUMBER") "RC0603JR-07100KL")
      )
      (libsource (lib "USB2.0_HUB_RES") (part "YAGEO RC0603JR-07100KL"))
    )
    (comp (ref "R50")
      (value "100k")
      (footprint "RES_0603")
      (description "RES 100kΩ ±5% 100mW 0603")
      (fields
        (field (name "MANUFACTURER") "YAGEO")
        (field (name "MANUFACTURER PART NUMBER") "RC0603JR-07100KL")
      )
      (libsource (lib "USB2.0_HUB_RES") (part "YAGEO RC0603JR-07100KL"))
    )
    (comp (ref "SW1")
      (value "PB")
      (footprint "ALPSALPINE SKRPABE010")
      (description "Tactile Switch SPST 2.5mm 4.2mm x 3.2mm Surface Mount")
      (fields
        (field (name "MANUFACTURER") "ALPSALPINE")
        (field (name "MANUFACTURER PART NUMBER") "SKRPABE010")
      )
      (libsource (lib "USB2.0_HUB") (part "ALPSALPINE SKRPABE010"))
    )
    (comp (ref "SW2")
      (value "PB")
      (footprint "ALPSALPINE SKRPABE010")
      (description "Tactile Switch SPST 2.5mm 4.2mm x 3.2mm Surface Mount")
      (fields
        (field (name "MANUFACTURER") "ALPSALPINE")
        (field (name "MANUFACTURER PART NUMBER") "SKRPABE010")
      )
      (libsource (lib "USB2.0_HUB") (part "ALPSALPINE SKRPABE010"))
    )
    (comp (ref "U1")
      (value "MIC2099-1YMT-TR")
      (footprint "MIC2099_UDFN-6")
      (description "UDFN-6 Power Distribution Switches, Load Drivers RoHS")
      (fields (field (name "MANUFACTURER") "MICROCHIP") (field (name "LCSC PART NUMBER") "C621526"))
      (libsource (lib "USB2.0_HUB") (part "MIC2099-1YMT-TR"))
    )
    (comp (ref "U2")
      (value "MIC2099-1YMT-TR")
      (footprint "MIC2099_UDFN-6")
      (description "UDFN-6 Power Distribution Switches, Load Drivers RoHS")
      (fields (field (name "MANUFACTURER") "MICROCHIP") (field (name "LCSC PART NUMBER") "C621526"))
      (libsource (lib "USB2.0_HUB") (part "MIC2099-1YMT-TR"))
    )
    (comp (ref "U3")
      (value "SPX3819M5-L-3-3/TR")
      (footprint "SPX3819M5-L-3-3/TR_SOT-23-5")
      (description "3.3V 16V Positive Fixed SOT-23-5 Voltage Regulators - Linear, Low Drop Out (LDO) Regulators RoHS")
      (fields (field (name "MANUFACTURER") "MaxLinear") (field (name "LCSC PART NUMBER") "C9055"))
      (libsource (lib "USB2.0_HUB") (part "MaxLinear SPX3819M5-L-3-3/TR"))
    )
    (comp (ref "U4")
      (value "SWITCH TACTILE SPST SMD")
      (footprint "XCVR_ESP32-S3-WROOM-1U")
      (description "2.4 GHz Wi-Fi (802.11 b/g/n) and Bluetooth 5 (LE) module")
      (fields
        (field (name "MANUFACTURER") "ESPRESSIF")
        (field (name "MANUFACTURER PART NUMBER") "ESP32-S3-WROOM-1U-N8")
      )
      (libsource (lib "USB2.0_HUB") (part "ESP32-S3-WROOM-1U-N8"))
    )
    (comp (ref "U5")
      (value "MIC2099-1YMT-TR")
      (footprint "MIC2099_UDFN-6")
      (description "UDFN-6 Power Distribution Switches, Load Drivers RoHS")
      (fields (field (name "MANUFACTURER") "MICROCHIP") (field (name "LCSC PART NUMBER") "C621526"))
      (libsource (lib "USB2.0_HUB") (part "MIC2099-1YMT-TR"))
    )
    (comp (ref "U6")
      (value "MIC2099-1YMT-TR")
      (footprint "MIC2099_UDFN-6")
      (description "UDFN-6 Power Distribution Switches, Load Drivers RoHS")
      (fields (field (name "MANUFACTURER") "MICROCHIP") (field (name "LCSC PART NUMBER") "C621526"))
      (libsource (lib "USB2.0_HUB") (part "MIC2099-1YMT-TR"))
    )
    (comp (ref "U7")
      (value "USB2514B-AEZC-TR")
      (footprint "USB2514B_VQFN-36-EP(6x6)")
      (description "4 480Mbps Hub USB 2.0 VQFN-36-EP(6x6) Interface Controllers RoHS")
      (fields (field (name "MANUFACTURER") "MICROCHIP") (field (name "LCSC PART NUMBER") "C16251"))
      (libsource (lib "USB2.0_HUB") (part "MICROCHIP USB2514B-AEZC-TR"))
    )
    (comp (ref "U10")
      (value "SPX3819M5-L-3-3/TR")
      (footprint "SPX3819M5-L-3-3/TR_SOT-23-5")
      (description "3.3V 16V Positive Fixed SOT-23-5 Voltage Regulators - Linear, Low Drop Out (LDO) Regulators RoHS")
      (fields (field (name "MANUFACTURER") "MaxLinear") (field (name "LCSC PART NUMBER") "C9055"))
      (libsource (lib "USB2.0_HUB") (part "MaxLinear SPX3819M5-L-3-3/TR"))
    )
    (comp (ref "X1")
      (value "24Mhz")
      (footprint "SMD3225-4P")
      (description "Crystal 24MHz ±10ppm 9pF 30Ω SMD3225-4P")
      (fields
        (field (name "MANUFACTURER") "TOGNJING")
        (field (name "MANUFACTURER PART NUMBER") "XTM32024000FT00351001")
      )
      (libsource (lib "USB2.0_HUB") (part "24MHz 4P"))
    )
  )
  (nets
    (net (code "1") (name "+3V3") (class "Default")
      (node (ref "C23") (pin "2") (pinfunction "2_2") (pintype "passive"))
      (node (ref "C24") (pin "2") (pinfunction "2_2") (pintype "passive"))
      (node (ref "C25") (pin "2") (pinfunction "2_2") (pintype "passive"))
      (node (ref "C26") (pin "2") (pinfunction "2_2") (pintype "passive"))
      (node (ref "C27") (pin "2") (pinfunction "2_2") (pintype "passive"))
      (node (ref "C28") (pin "2") (pinfunction "2_2") (pintype "passive"))
      (node (ref "C29") (pin "2") (pinfunction "2_2") (pintype "passive"))
      (node (ref "C7") (pin "2") (pinfunction "2_2") (pintype "passive"))
      (node (ref "R47") (pin "2") (pinfunction "2_2") (pintype "passive"))
      (node (ref "R48") (pin "2") (pinfunction "2_2") (pintype "passive"))
      (node (ref "R49") (pin "2") (pinfunction "2_2") (pintype "passive"))
      (node (ref "R50") (pin "2") (pinfunction "2_2") (pintype "passive"))
      (node (ref "U3") (pin "5") (pinfunction "VOUT_5") (pintype "power_in"))
      (node (ref "U7") (pin "10") (pinfunction "VDDA3V3_10") (pintype "power_in"))
      (node (ref "U7") (pin "15") (pinfunction "VDD3V3_15") (pintype "power_in"))
      (node (ref "U7") (pin "23") (pinfunction "VDD3V3_23") (pintype "power_in"))
      (node (ref "U7") (pin "26") (pinfunction "RESET_N_26") (pintype "input"))
      (node (ref "U7") (pin "29") (pinfunction "VDDA3V3_29") (pintype "output"))
      (node (ref "U7") (pin "36") (pinfunction "VDD3V3_36") (pintype "power_in"))
      (node (ref "U7") (pin "5") (pinfunction "VDDA3V3_5") (pintype "power_in"))
    )
    (net (code "2") (name "+3V3 ESP1") (class "Default")
      (node (ref "C37") (pin "2") (pinfunction "2_2") (pintype "passive"))
      (node (ref "C4") (pin "2") (pinfunction "2_2") (pintype "passive"))
      (node (ref "J2") (pin "1") (pinfunction "1_1") (pintype "passive"))
      (node (ref "J7") (pin "1") (pinfunction "1_1") (pintype "passive"))
      (node (ref "J8") (pin "1") (pinfunction "1_1") (pintype "passive"))
      (node (ref "J9") (pin "1") (pinfunction "1_1") (pintype "passive"))
      (node (ref "R3") (pin "2") (pinfunction "2_2") (pintype "passive"))
      (node (ref "R9") (pin "2") (pinfunction "2_2") (pintype "passive"))
      (node (ref "U10") (pin "5") (pinfunction "VOUT_5") (pintype "power_in"))
      (node (ref "U4") (pin "2") (pinfunction "3V3_2") (pintype "power_in"))
    )
    (net (code "3") (name "+5V FILT PORT1") (class "Default")
      (node (ref "D5") (pin "5") (pinfunction "VBUS_5") (pintype "power_in"))
      (node (ref "FB3") (pin "2") (pinfunction "2_2") (pintype "passive"))
      (node (ref "J4") (pin "1") (pinfunction "VCC_1") (pintype "power_in"))
    )
    (net (code "4") (name "+5V FILT PORT2") (class "Default")
      (node (ref "C43") (pin "1") (pinfunction "1_1") (pintype "passive"))
      (node (ref "D4") (pin "5") (pinfunction "VBUS_5") (pintype "power_in"))
      (node (ref "FB4") (pin "2") (pinfunction "2_2") (pintype "passive"))
      (node (ref "J5") (pin "A4_B9") (pinfunction "VBUS_A_A4_B9") (pintype "power_in"))
      (node (ref "J5") (pin "B4_A9") (pinfunction "VBUS_B_B4_A9") (pintype "power_in"))
      (node (ref "R41") (pin "2") (pinfunction "2_2") (pintype "passive"))
      (node (ref "R42") (pin "2") (pinfunction "2_2") (pintype "passive"))
    )
    (net (code "5") (name "+5V FILT PORT4") (class "Default")
      (node (ref "C32") (pin "1") (pinfunction "1_1") (pintype "passive"))
      (node (ref "D2") (pin "5") (pinfunction "VBUS_5") (pintype "power_in"))
      (node (ref "FB2") (pin "2") (pinfunction "2_2") (pintype "passive"))
      (node (ref "J6") (pin "1") (pinfunction "VCC_1") (pintype "power_in"))
    )
    (net (code "6") (name "+5V HOST") (class "Default")
      (node (ref "C15") (pin "2") (pinfunction "2_2") (pintype "passive"))
      (node (ref "D1") (pin "5") (pinfunction "VBUS_5") (pintype "power_in"))
      (node (ref "FB1") (pin "1") (pinfunction "1_1") (pintype "passive"))
      (node (ref "Q1") (pin "1") (pinfunction "S_1") (pintype "passive"))
      (node (ref "Q1") (pin "2") (pinfunction "S_2") (pintype "passive"))
      (node (ref "Q1") (pin "3") (pinfunction "S_3") (pintype "passive"))
      (node (ref "Q2") (pin "1") (pinfunction "S_1") (pintype "passive"))
      (node (ref "Q2") (pin "2") (pinfunction "S_2") (pintype "passive"))
      (node (ref "Q2") (pin "3") (pinfunction "S_3") (pintype "passive"))
      (node (ref "R1") (pin "2") (pinfunction "2_2") (pintype "passive"))
      (node (ref "R15") (pin "2") (pinfunction "2_2") (pintype "passive"))
      (node (ref "R29") (pin "2") (pinfunction "2_2") (pintype "passive"))
    )
    (net (code "7") (name "+5V HOST FILT") (class "Default")
      (node (ref "C1") (pin "2") (pinfunction "2_2") (pintype "passive"))
      (node (ref "C11") (pin "2") (pinfunction "2_2") (pintype "passive"))
      (node (ref "C12") (pin "2") (pinfunction "2_2") (pintype "passive"))
      (node (ref "C16") (pin "2") (pinfunction "2_2") (pintype "passive"))
      (node (ref "C2") (pin "2") (pinfunction "2_2") (pintype "passive"))
      (node (ref "C6") (pin "2") (pinfunction "2_2") (pintype "passive"))
      (node (ref "FB1") (pin "2") (pinfunction "2_2") (pintype "passive"))
      (node (ref "R10") (pin "2") (pinfunction "2_2") (pintype "passive"))
      (node (ref "R11") (pin "2") (pinfunction "2_2") (pintype "passive"))
      (node (ref "R2") (pin "2") (pinfunction "2_2") (pintype "passive"))
      (node (ref "R25") (pin "2") (pinfunction "2_2") (pintype "passive"))
      (node (ref "R4") (pin "2") (pinfunction "2_2") (pintype "passive"))
      (node (ref "R5") (pin "2") (pinfunction "2_2") (pintype "passive"))
      (node (ref "U1") (pin "6") (pinfunction "VIN_6") (pintype "passive"))
      (node (ref "U2") (pin "6") (pinfunction "VIN_6") (pintype "passive"))
      (node (ref "U3") (pin "1") (pinfunction "VIN_1") (pintype "power_in"))
      (node (ref "U5") (pin "6") (pinfunction "VIN_6") (pintype "passive"))
      (node (ref "U6") (pin "6") (pinfunction "VIN_6") (pintype "passive"))
    )
    (net (code "8") (name "+5V HOST IN") (class "Default")
      (node (ref "J3") (pin "1") (pinfunction "VCC_1") (pintype "power_in"))
      (node (ref "Q2") (pin "5") (pinfunction "D_5") (pintype "passive"))
      (node (ref "Q2") (pin "6") (pinfunction "D_6") (pintype "passive"))
      (node (ref "Q2") (pin "7") (pinfunction "D_7") (pintype "passive"))
      (node (ref "Q2") (pin "8") (pinfunction "D_8") (pintype "passive"))
    )
    (net (code "9") (name "+5V PORT1") (class "Default")
      (node (ref "C3") (pin "2") (pinfunction "2_2") (pintype "passive"))
      (node (ref "C31") (pin "2") (pinfunction "2_2") (pintype "passive"))
      (node (ref "FB3") (pin "1") (pinfunction "1_1") (pintype "passive"))
      (node (ref "R43") (pin "2") (pinfunction "2_2") (pintype "passive"))
      (node (ref "U1") (pin "1") (pinfunction "VOUT_1") (pintype "passive"))
    )
    (net (code "10") (name "+5V PORT2") (class "Default")
      (node (ref "C44") (pin "2") (pinfunction "2_2") (pintype "passive"))
      (node (ref "C5") (pin "2") (pinfunction "2_2") (pintype "passive"))
      (node (ref "FB4") (pin "1") (pinfunction "1_1") (pintype "passive"))
      (node (ref "R44") (pin "2") (pinfunction "2_2") (pintype "passive"))
      (node (ref "U2") (pin "1") (pinfunction "VOUT_1") (pintype "passive"))
    )
    (net (code "11") (name "+5V PORT3") (class "Default")
      (node (ref "C13") (pin "2") (pinfunction "2_2") (pintype "passive"))
      (node (ref "D3") (pin "5") (pinfunction "VBUS_5") (pintype "power_in"))
      (node (ref "R31") (pin "1") (pinfunction "1_1") (pintype "passive"))
      (node (ref "R45") (pin "2") (pinfunction "2_2") (pintype "passive"))
      (node (ref "U5") (pin "1") (pinfunction "VOUT_1") (pintype "passive"))
    )
    (net (code "12") (name "+5V PORT4") (class "Default")
      (node (ref "C14") (pin "2") (pinfunction "2_2") (pintype "passive"))
      (node (ref "C34") (pin "2") (pinfunction "2_2") (pintype "passive"))
      (node (ref "FB2") (pin "1") (pinfunction "1_1") (pintype "passive"))
      (node (ref "R46") (pin "2") (pinfunction "2_2") (pintype "passive"))
      (node (ref "U6") (pin "1") (pinfunction "VOUT_1") (pintype "passive"))
    )
    (net (code "13") (name "+5V VBUS_EXT") (class "Default")
      (node (ref "J1") (pin "A4_B9") (pinfunction "VBUS_A_A4_B9") (pintype "power_in"))
      (node (ref "J1") (pin "B4_A9") (pinfunction "VBUS_B_B4_A9") (pintype "power_in"))
      (node (ref "Q1") (pin "5") (pinfunction "D_5") (pintype "passive"))
      (node (ref "Q1") (pin "6") (pinfunction "D_6") (pintype "passive"))
      (node (ref "Q1") (pin "7") (pinfunction "D_7") (pintype "passive"))
      (node (ref "Q1") (pin "8") (pinfunction "D_8") (pintype "passive"))
    )
    (net (code "14") (name "/BYP") (class "Default")
      (node (ref "C9") (pin "2") (pinfunction "2_2") (pintype "passive"))
      (node (ref "U3") (pin "4") (pinfunction "BYP_4") (pintype "passive"))
    )
    (net (code "15") (name "/BYP ESP1") (class "Default")
      (node (ref "C40") (pin "2") (pinfunction "2_2") (pintype "passive"))
      (node (ref "U10") (pin "4") (pinfunction "BYP_4") (pintype "passive"))
    )
    (net (code "16") (name "/EN ESP1") (class "Default")
      (node (ref "R34") (pin "1") (pinfunction "1_1") (pintype "passive"))
      (node (ref "R36") (pin "2") (pinfunction "2_2") (pintype "passive"))
      (node (ref "U10") (pin "3") (pinfunction "EN_3") (pintype "input"))
    )
    (net (code "17") (name "/ESP1_DTR") (class "Default")
      (node (ref "J2") (pin "2") (pinfunction "2_2") (pintype "passive"))
      (node (ref "Q4") (pin "2") (pinfunction "E_2") (pintype "passive"))
      (node (ref "R16") (pin "2") (pinfunction "2_2") (pintype "passive"))
    )
    (net (code "18") (name "/ESP1_EN") (class "Default")
      (node (ref "C8") (pin "2") (pinfunction "2_2") (pintype "passive"))
      (node (ref "R14") (pin "2") (pinfunction "2_2") (pintype "passive"))
      (node (ref "R3") (pin "1") (pinfunction "1_1") (pintype "passive"))
      (node (ref "SW1") (pin "3") (pinfunction "2_3") (pintype "passive"))
      (node (ref "SW1") (pin "4") (pinfunction "2_4") (pintype "passive"))
      (node (ref "U4") (pin "3") (pinfunction "EN_3") (pintype "passive"))
    )
    (net (code "19") (name "/ESP1_IO0") (class "Default")
      (node (ref "C10") (pin "2") (pinfunction "2_2") (pintype "passive"))
      (node (ref "R19") (pin "2") (pinfunction "2_2") (pintype "passive"))
      (node (ref "R9") (pin "1") (pinfunction "1_1") (pintype "passive"))
      (node (ref "SW2") (pin "3") (pinfunction "2_3") (pintype "passive"))
      (node (ref "SW2") (pin "4") (pinfunction "2_4") (pintype "passive"))
      (node (ref "U4") (pin "27") (pinfunction "IO0_27") (pintype "passive"))
    )
    (net (code "20") (name "/ESP1_RTS") (class "Default")
      (node (ref "J2") (pin "3") (pinfunction "3_3") (pintype "passive"))
      (node (ref "Q3") (pin "2") (pinfunction "E_2") (pintype "passive"))
      (node (ref "R18") (pin "2") (pinfunction "2_2") (pintype "passive"))
    )
    (net (code "21") (name "/ESP1_RX") (class "Default")
      (node (ref "J2") (pin "4") (pinfunction "4_4") (pintype "passive"))
      (node (ref "U4") (pin "36") (pinfunction "RXD0_36") (pintype "passive"))
    )
    (net (code "22") (name "/ESP1_SCL") (class "Default")
      (node (ref "J7") (pin "2") (pinfunction "2_2") (pintype "passive"))
      (node (ref "J8") (pin "2") (pinfunction "2_2") (pintype "passive"))
      (node (ref "U4") (pin "17") (pinfunction "IO9_17") (pintype "passive"))
    )
    (net (code "23") (name "/ESP1_SDA") (class "Default")
      (node (ref "J7") (pin "3") (pinfunction "3_3") (pintype "passive"))
      (node (ref "J8") (pin "3") (pinfunction "3_3") (pintype "passive"))
      (node (ref "U4") (pin "12") (pinfunction "IO8_12") (pintype "passive"))
    )
    (net (code "24") (name "/ESP1_TX") (class "Default")
      (node (ref "J2") (pin "5") (pinfunction "5_5") (pintype "passive"))
      (node (ref "U4") (pin "37") (pinfunction "TXD0_37") (pintype "passive"))
    )
    (net (code "25") (name "/PORT1_ILIM") (class "Default")
      (node (ref "R6") (pin "2") (pinfunction "2_2") (pintype "passive"))
      (node (ref "U1") (pin "2") (pinfunction "ILIMT_2") (pintype "passive"))
    )
    (net (code "26") (name "/PORT2_ILIM") (class "Default")
      (node (ref "R8") (pin "2") (pinfunction "2_2") (pintype "passive"))
      (node (ref "U2") (pin "2") (pinfunction "ILIMT_2") (pintype "passive"))
    )
    (net (code "27") (name "/PORT3_ILIM") (class "Default")
      (node (ref "R12") (pin "2") (pinfunction "2_2") (pintype "passive"))
      (node (ref "U5") (pin "2") (pinfunction "ILIMT_2") (pintype "passive"))
    )
    (net (code "28") (name "/PORT4_ILIM") (class "Default")
      (node (ref "R13") (pin "2") (pinfunction "2_2") (pintype "passive"))
      (node (ref "U6") (pin "2") (pinfunction "ILIMT_2") (pintype "passive"))
    )
    (net (code "29") (name "/S_AN") (class "Default")
      (node (ref "J9") (pin "3") (pinfunction "3_3") (pintype "passive"))
      (node (ref "U4") (pin "9") (pinfunction "IO16_9") (pintype "passive"))
    )
    (net (code "30") (name "/S_EN") (class "Default")
      (node (ref "J9") (pin "2") (pinfunction "2_2") (pintype "passive"))
      (node (ref "U4") (pin "8") (pinfunction "IO15_8") (pintype "passive"))
    )
    (net (code "31") (name "/USB_HOST_A_D_N") (class "Default")
      (node (ref "D1") (pin "4") (pinfunction "I/O2_OUT_4") (pintype "bidirectional"))
      (node (ref "J3") (pin "2") (pinfunction "D-_2") (pintype "bidirectional"))
    )
    (net (code "32") (name "/USB_HOST_A_D_P") (class "Default")
      (node (ref "D1") (pin "6") (pinfunction "I/O1_OUT_6") (pintype "bidirectional"))
      (node (ref "J3") (pin "3") (pinfunction "D+_3") (pintype "bidirectional"))
    )
    (net (code "33") (name "/USB_HOST_D_N") (class "Default")
      (node (ref "D1") (pin "3") (pinfunction "I/O2_IN_3") (pintype "bidirectional"))
      (node (ref "U7") (pin "30") (pinfunction "USBDM_UP_30") (pintype "bidirectional"))
    )
    (net (code "34") (name "/USB_HOST_D_P") (class "Default")
      (node (ref "D1") (pin "1") (pinfunction "I/O1_IN_1") (pintype "bidirectional"))
      (node (ref "U7") (pin "31") (pinfunction "USBDP_UP_31") (pintype "bidirectional"))
    )
    (net (code "35") (name "/USB_HUB1_D_N") (class "Default")
      (node (ref "D5") (pin "3") (pinfunction "I/O2_IN_3") (pintype "bidirectional"))
      (node (ref "U7") (pin "1") (pinfunction "USBDM_DN1/PRT_DIS_M1_1") (pintype "bidirectional"))
    )
    (net (code "36") (name "/USB_HUB1_D_P") (class "Default")
      (node (ref "D5") (pin "1") (pinfunction "I/O1_IN_1") (pintype "bidirectional"))
      (node (ref "U7") (pin "2") (pinfunction "USBDP_DN1/PRT_DIS_P1_2") (pintype "bidirectional"))
    )
    (net (code "37") (name "/USB_HUB2_D_N") (class "Default")
      (node (ref "D4") (pin "3") (pinfunction "I/O2_IN_3") (pintype "bidirectional"))
      (node (ref "U7") (pin "3") (pinfunction "USBDM_DN2/PRT_DIS_M2_3") (pintype "bidirectional"))
    )
    (net (code "38") (name "/USB_HUB2_D_P") (class "Default")
      (node (ref "D4") (pin "1") (pinfunction "I/O1_IN_1") (pintype "bidirectional"))
      (node (ref "U7") (pin "4") (pinfunction "USBDP_DN2/PRT_DIS_P2_4") (pintype "bidirectional"))
    )
    (net (code "39") (name "/USB_HUB3_D_N") (class "Default")
      (node (ref "D3") (pin "1") (pinfunction "I/O1_IN_1") (pintype "bidirectional"))
      (node (ref "U7") (pin "6") (pinfunction "USBDM_DN3/PRT_DIS_M3_6") (pintype "bidirectional"))
    )
    (net (code "40") (name "/USB_HUB3_D_P") (class "Default")
      (node (ref "D3") (pin "3") (pinfunction "I/O2_IN_3") (pintype "bidirectional"))
      (node (ref "U7") (pin "7") (pinfunction "USBDP_DN3/PRT_DIS_P3_7") (pintype "bidirectional"))
    )
    (net (code "41") (name "/USB_HUB4_D_N") (class "Default")
      (node (ref "D2") (pin "3") (pinfunction "I/O2_IN_3") (pintype "bidirectional"))
      (node (ref "U7") (pin "8") (pinfunction "USBDM_DN4/PRT_DIS_M4_8") (pintype "bidirectional"))
    )
    (net (code "42") (name "/USB_HUB4_D_P") (class "Default")
      (node (ref "D2") (pin "1") (pinfunction "I/O1_IN_1") (pintype "bidirectional"))
      (node (ref "U7") (pin "9") (pinfunction "USBDP_DN4/PRT_DIS_P4_9") (pintype "bidirectional"))
    )
    (net (code "43") (name "/USB_HUB_CRFILT") (class "Default")
      (node (ref "C21") (pin "2") (pinfunction "2_2") (pintype "passive"))
      (node (ref "C22") (pin "2") (pinfunction "2_2") (pintype "passive"))
      (node (ref "U7") (pin "14") (pinfunction "CRFILT_14") (pintype "output"))
    )
    (net (code "44") (name "/USB_HUB_HS_IND") (class "Default")
      (node (ref "R21") (pin "2") (pinfunction "2_2") (pintype "passive"))
      (node (ref "R48") (pin "1") (pinfunction "1_1") (pintype "passive"))
      (node (ref "U7") (pin "25") (pinfunction "HS_IND/CFG_SEL1_25") (pintype "output"))
    )
    (net (code "45") (name "/USB_HUB_NOCS1") (class "Default")
      (node (ref "R2") (pin "1") (pinfunction "1_1") (pintype "passive"))
      (node (ref "U1") (pin "3") (pinfunction "NFAULT_3") (pintype "passive"))
      (node (ref "U7") (pin "13") (pinfunction "OCS_N1_13") (pintype "bidirectional"))
    )
    (net (code "46") (name "/USB_HUB_NOCS2") (class "Default")
      (node (ref "R4") (pin "1") (pinfunction "1_1") (pintype "passive"))
      (node (ref "U2") (pin "3") (pinfunction "NFAULT_3") (pintype "passive"))
      (node (ref "U7") (pin "17") (pinfunction "OCS_N2_17") (pintype "bidirectional"))
    )
    (net (code "47") (name "/USB_HUB_NOCS3") (class "Default")
      (node (ref "R10") (pin "1") (pinfunction "1_1") (pintype "passive"))
      (node (ref "U5") (pin "3") (pinfunction "NFAULT_3") (pintype "passive"))
      (node (ref "U7") (pin "19") (pinfunction "OCS_N3_19") (pintype "bidirectional"))
    )
    (net (code "48") (name "/USB_HUB_NOCS4") (class "Default")
      (node (ref "R11") (pin "1") (pinfunction "1_1") (pintype "passive"))
      (node (ref "U6") (pin "3") (pinfunction "NFAULT_3") (pintype "passive"))
      (node (ref "U7") (pin "21") (pinfunction "OCS_N4_21") (pintype "bidirectional"))
    )
    (net (code "49") (name "/USB_HUB_PLLFILT") (class "Default")
      (node (ref "C19") (pin "2") (pinfunction "2_2") (pintype "passive"))
      (node (ref "C20") (pin "2") (pinfunction "2_2") (pintype "passive"))
      (node (ref "U7") (pin "34") (pinfunction "PLLFILT_34") (pintype "output"))
    )
    (net (code "50") (name "/USB_HUB_PRTPWR1") (class "Default")
      (node (ref "U1") (pin "4") (pinfunction "EN_4") (pintype "passive"))
      (node (ref "U7") (pin "12") (pinfunction "PRTPWR1/BC_EN1_12") (pintype "input"))
    )
    (net (code "51") (name "/USB_HUB_PRTPWR2") (class "Default")
      (node (ref "U2") (pin "4") (pinfunction "EN_4") (pintype "passive"))
      (node (ref "U7") (pin "16") (pinfunction "PRTPWR2/BC_EN2_16") (pintype "input"))
    )
    (net (code "52") (name "/USB_HUB_PRTPWR3") (class "Default")
      (node (ref "U5") (pin "4") (pinfunction "EN_4") (pintype "passive"))
      (node (ref "U7") (pin "18") (pinfunction "PRTPWR3/BC_EN3_18") (pintype "input"))
    )
    (net (code "53") (name "/USB_HUB_PRTPWR4") (class "Default")
      (node (ref "U6") (pin "4") (pinfunction "EN_4") (pintype "passive"))
      (node (ref "U7") (pin "20") (pinfunction "PRTPWR4/BC_EN4_20") (pintype "input"))
    )
    (net (code "54") (name "/USB_HUB_RBIAS") (class "Default")
      (node (ref "R24") (pin "1") (pinfunction "1_1") (pintype "passive"))
      (node (ref "U7") (pin "35") (pinfunction "RBIAS_35") (pintype "output"))
    )
    (net (code "55") (name "/USB_HUB_SCL") (class "Default")
      (node (ref "R20") (pin "2") (pinfunction "2_2") (pintype "passive"))
      (node (ref "R47") (pin "1") (pinfunction "1_1") (pintype "passive"))
      (node (ref "U7") (pin "24") (pinfunction "SCL/SMBCLK/CFG_SEL0_24") (pintype "output"))
    )
    (net (code "56") (name "/USB_HUB_SDA") (class "Default")
      (node (ref "R23") (pin "2") (pinfunction "2_2") (pintype "passive"))
      (node (ref "R50") (pin "1") (pinfunction "1_1") (pintype "passive"))
      (node (ref "U7") (pin "22") (pinfunction "SDA/SMBDATA/NON_REM1_22") (pintype "bidirectional"))
    )
    (net (code "57") (name "/USB_HUB_SUSP_IND") (class "Default")
      (node (ref "R22") (pin "2") (pinfunction "2_2") (pintype "passive"))
      (node (ref "R49") (pin "1") (pinfunction "1_1") (pintype "passive"))
      (node (ref "U7") (pin "28") (pinfunction "SUSP_IND/LOCAL_PWR/NON_REM0_28") (pintype "bidirectional"))
    )
    (net (code "58") (name "/USB_HUB_XTALIN") (class "Default")
      (node (ref "C18") (pin "2") (pinfunction "2_2") (pintype "passive"))
      (node (ref "U7") (pin "33") (pinfunction "XTALIN/CLKIN_33") (pintype "input"))
      (node (ref "X1") (pin "3") (pinfunction "3_3") (pintype "passive"))
    )
    (net (code "59") (name "/USB_HUB_XTALOUT") (class "Default")
      (node (ref "C17") (pin "2") (pinfunction "2_2") (pintype "passive"))
      (node (ref "U7") (pin "32") (pinfunction "XTALOUT_32") (pintype "output"))
      (node (ref "X1") (pin "1") (pinfunction "1_1") (pintype "passive"))
    )
    (net (code "60") (name "/USB_PORT1_D_N") (class "Default")
      (node (ref "D5") (pin "4") (pinfunction "I/O2_OUT_4") (pintype "bidirectional"))
      (node (ref "J4") (pin "2") (pinfunction "D-_2") (pintype "bidirectional"))
    )
    (net (code "61") (name "/USB_PORT1_D_P") (class "Default")
      (node (ref "D5") (pin "6") (pinfunction "I/O1_OUT_6") (pintype "bidirectional"))
      (node (ref "J4") (pin "3") (pinfunction "D+_3") (pintype "bidirectional"))
    )
    (net (code "62") (name "/USB_PORT2_D_N") (class "Default")
      (node (ref "D4") (pin "4") (pinfunction "I/O2_OUT_4") (pintype "bidirectional"))
      (node (ref "J5") (pin "A7") (pinfunction "D1-_A7") (pintype "bidirectional"))
      (node (ref "J5") (pin "B7") (pinfunction "D2-_B7") (pintype "bidirectional"))
    )
    (net (code "63") (name "/USB_PORT2_D_P") (class "Default")
      (node (ref "D4") (pin "6") (pinfunction "I/O1_OUT_6") (pintype "bidirectional"))
      (node (ref "J5") (pin "A6") (pinfunction "D1+_A6") (pintype "bidirectional"))
      (node (ref "J5") (pin "B6") (pinfunction "D2+_B6") (pintype "bidirectional"))
    )
    (net (code "64") (name "/USB_PORT3_D_N") (class "Default")
      (node (ref "D3") (pin "6") (pinfunction "I/O1_OUT_6") (pintype "bidirectional"))
      (node (ref "U4") (pin "13") (pinfunction "IO19_13") (pintype "passive"))
    )
    (net (code "65") (name "/USB_PORT3_D_P") (class "Default")
      (node (ref "D3") (pin "4") (pinfunction "I/O2_OUT_4") (pintype "bidirectional"))
      (node (ref "U4") (pin "14") (pinfunction "IO20_14") (pintype "passive"))
    )
    (net (code "66") (name "/USB_PORT4_D_N") (class "Default")
      (node (ref "D2") (pin "4") (pinfunction "I/O2_OUT_4") (pintype "bidirectional"))
      (node (ref "J6") (pin "2") (pinfunction "D-_2") (pintype "bidirectional"))
    )
    (net (code "67") (name "/USB_PORT4_D_P") (class "Default")
      (node (ref "D2") (pin "6") (pinfunction "I/O1_OUT_6") (pintype "bidirectional"))
      (node (ref "J6") (pin "3") (pinfunction "D+_3") (pintype "bidirectional"))
    )
    (net (code "68") (name "/VBUS_DET") (class "Default")
      (node (ref "R25") (pin "1") (pinfunction "1_1") (pintype "passive"))
      (node (ref "R26") (pin "2") (pinfunction "2_2") (pintype "passive"))
      (node (ref "U3") (pin "3") (pinfunction "EN_3") (pintype "input"))
      (node (ref "U7") (pin "27") (pinfunction "VBUS_DET_27") (pintype "input"))
    )
    (net (code "69") (name "/VIN_ESP1") (class "Default")
      (node (ref "C36") (pin "2") (pinfunction "2_2") (pintype "passive"))
      (node (ref "R29") (pin "1") (pinfunction "1_1") (pintype "passive"))
      (node (ref "R31") (pin "2") (pinfunction "2_2") (pintype "passive"))
      (node (ref "R34") (pin "2") (pinfunction "2_2") (pintype "passive"))
      (node (ref "U10") (pin "1") (pinfunction "VIN_1") (pintype "power_in"))
    )
    (net (code "70") (name "GND") (class "Default")
      (node (ref "C1") (pin "1") (pinfunction "1_1") (pintype "passive"))
      (node (ref "C10") (pin "1") (pinfunction "1_1") (pintype "passive"))
      (node (ref "C11") (pin "1") (pinfunction "1_1") (pintype "passive"))
      (node (ref "C12") (pin "1") (pinfunction "1_1") (pintype "passive"))
      (node (ref "C13") (pin "1") (pinfunction "1_1") (pintype "passive"))
      (node (ref "C14") (pin "1") (pinfunction "1_1") (pintype "passive"))
      (node (ref "C15") (pin "1") (pinfunction "1_1") (pintype "passive"))
      (node (ref "C16") (pin "1") (pinfunction "1_1") (pintype "passive"))
      (node (ref "C17") (pin "1") (pinfunction "1_1") (pintype "passive"))
      (node (ref "C18") (pin "1") (pinfunction "1_1") (pintype "passive"))
      (node (ref "C19") (pin "1") (pinfunction "1_1") (pintype "passive"))
      (node (ref "C2") (pin "1") (pinfunction "1_1") (pintype "passive"))
      (node (ref "C20") (pin "1") (pinfunction "1_1") (pintype "passive"))
      (node (ref "C21") (pin "1") (pinfunction "1_1") (pintype "passive"))
      (node (ref "C22") (pin "1") (pinfunction "1_1") (pintype "passive"))
      (node (ref "C23") (pin "1") (pinfunction "1_1") (pintype "passive"))
      (node (ref "C24") (pin "1") (pinfunction "1_1") (pintype "passive"))
      (node (ref "C25") (pin "1") (pinfunction "1_1") (pintype "passive"))
      (node (ref "C26") (pin "1") (pinfunction "1_1") (pintype "passive"))
      (node (ref "C27") (pin "1") (pinfunction "1_1") (pintype "passive"))
      (node (ref "C28") (pin "1") (pinfunction "1_1") (pintype "passive"))
      (node (ref "C29") (pin "1") (pinfunction "1_1") (pintype "passive"))
      (node (ref "C3") (pin "1") (pinfunction "1_1") (pintype "passive"))
      (node (ref "C31") (pin "1") (pinfunction "1_1") (pintype "passive"))
      (node (ref "C32") (pin "2") (pinfunction "2_2") (pintype "passive"))
      (node (ref "C33") (pin "2") (pinfunction "2_2") (pintype "passive"))
      (node (ref "C34") (pin "1") (pinfunction "1_1") (pintype "passive"))
      (node (ref "C35") (pin "2") (pinfunction "2_2") (pintype "passive"))
      (node (ref "C36") (pin "1") (pinfunction "1_1") (pintype "passive"))
      (node (ref "C37") (pin "1") (pinfunction "1_1") (pintype "passive"))
      (node (ref "C38") (pin "1") (pinfunction "1_1") (pintype "passive"))
      (node (ref "C4") (pin "1") (pinfunction "1_1") (pintype "passive"))
      (node (ref "C40") (pin "1") (pinfunction "1_1") (pintype "passive"))
      (node (ref "C43") (pin "2") (pinfunction "2_2") (pintype "passive"))
      (node (ref "C44") (pin "1") (pinfunction "1_1") (pintype "passive"))
      (node (ref "C45") (pin "1") (pinfunction "1_1") (pintype "passive"))
      (node (ref "C46") (pin "1") (pinfunction "1_1") (pintype "passive"))
      (node (ref "C5") (pin "1") (pinfunction "1_1") (pintype "passive"))
      (node (ref "C6") (pin "1") (pinfunction "1_1") (pintype "passive"))
      (node (ref "C7") (pin "1") (pinfunction "1_1") (pintype "passive"))
      (node (ref "C8") (pin "1") (pinfunction "1_1") (pintype "passive"))
      (node (ref "C9") (pin "1") (pinfunction "1_1") (pintype "passive"))
      (node (ref "D1") (pin "2") (pinfunction "GND_2") (pintype "power_in"))
      (node (ref "D10") (pin "C") (pinfunction "C_C") (pintype "passive"))
      (node (ref "D2") (pin "2") (pinfunction "GND_2") (pintype "power_in"))
      (node (ref "D3") (pin "2") (pinfunction "GND_2") (pintype "power_in"))
      (node (ref "D4") (pin "2") (pinfunction "GND_2") (pintype "power_in"))
      (node (ref "D5") (pin "2") (pinfunction "GND_2") (pintype "power_in"))
      (node (ref "D6") (pin "C") (pinfunction "C_C") (pintype "passive"))
      (node (ref "D7") (pin "C") (pinfunction "C_C") (pintype "passive"))
      (node (ref "D8") (pin "C") (pinfunction "C_C") (pintype "passive"))
      (node (ref "D9") (pin "C") (pinfunction "C_C") (pintype "passive"))
      (node (ref "J1") (pin "A1_B12") (pinfunction "GND_A_A1_B12") (pintype "power_in"))
      (node (ref "J1") (pin "B1_A12") (pinfunction "GND_B_B1_A12") (pintype "power_in"))
      (node (ref "J2") (pin "6") (pinfunction "6_6") (pintype "passive"))
      (node (ref "J3") (pin "4") (pinfunction "GND_4") (pintype "power_in"))
      (node (ref "J4") (pin "4") (pinfunction "GND_4") (pintype "power_in"))
      (node (ref "J5") (pin "A1_B12") (pinfunction "GND_A_A1_B12") (pintype "power_in"))
      (node (ref "J5") (pin "B1_A12") (pinfunction "GND_B_B1_A12") (pintype "power_in"))
      (node (ref "J6") (pin "4") (pinfunction "GND_4") (pintype "power_in"))
      (node (ref "J7") (pin "4") (pinfunction "4_4") (pintype "passive"))
      (node (ref "J8") (pin "4") (pinfunction "4_4") (pintype "passive"))
      (node (ref "J9") (pin "4") (pinfunction "4_4") (pintype "passive"))
      (node (ref "M1") (pin "1") (pinfunction "H_1") (pintype "passive"))
      (node (ref "M2") (pin "1") (pinfunction "H_1") (pintype "passive"))
      (node (ref "M3") (pin "1") (pinfunction "H_1") (pintype "passive"))
      (node (ref "M4") (pin "1") (pinfunction "H_1") (pintype "passive"))
      (node (ref "M5") (pin "1") (pinfunction "H_1") (pintype "passive"))
      (node (ref "R12") (pin "1") (pinfunction "1_1") (pintype "passive"))
      (node (ref "R13") (pin "1") (pinfunction "1_1") (pintype "passive"))
      (node (ref "R17") (pin "1") (pinfunction "1_1") (pintype "passive"))
      (node (ref "R20") (pin "1") (pinfunction "1_1") (pintype "passive"))
      (node (ref "R21") (pin "1") (pinfunction "1_1") (pintype "passive"))
      (node (ref "R22") (pin "1") (pinfunction "1_1") (pintype "passive"))
      (node (ref "R23") (pin "1") (pinfunction "1_1") (pintype "passive"))
      (node (ref "R24") (pin "2") (pinfunction "2_2") (pintype "passive"))
      (node (ref "R26") (pin "1") (pinfunction "1_1") (pintype "passive"))
      (node (ref "R36") (pin "1") (pinfunction "1_1") (pintype "passive"))
      (node (ref "R6") (pin "1") (pinfunction "1_1") (pintype "passive"))
      (node (ref "R7") (pin "1") (pinfunction "1_1") (pintype "passive"))
      (node (ref "R8") (pin "1") (pinfunction "1_1") (pintype "passive"))
      (node (ref "SW1") (pin "1") (pinfunction "1_1") (pintype "passive"))
      (node (ref "SW1") (pin "2") (pinfunction "1_2") (pintype "passive"))
      (node (ref "SW2") (pin "1") (pinfunction "1_1") (pintype "passive"))
      (node (ref "SW2") (pin "2") (pinfunction "1_2") (pintype "passive"))
      (node (ref "U1") (pin "5") (pinfunction "GND_5") (pintype "passive"))
      (node (ref "U1") (pin "7") (pinfunction "EP_7") (pintype "passive"))
      (node (ref "U10") (pin "2") (pinfunction "GND_2") (pintype "power_in"))
      (node (ref "U2") (pin "5") (pinfunction "GND_5") (pintype "passive"))
      (node (ref "U2") (pin "7") (pinfunction "EP_7") (pintype "passive"))
      (node (ref "U3") (pin "2") (pinfunction "GND_2") (pintype "power_in"))
      (node (ref "U4") (pin "1") (pinfunction "GND_1") (pintype "power_in"))
      (node (ref "U4") (pin "40") (pinfunction "GND_40") (pintype "power_in"))
      (node (ref "U4") (pin "41_1") (pinfunction "GND_41_1") (pintype "power_in"))
      (node (ref "U4") (pin "41_2") (pinfunction "GND_41_2") (pintype "power_in"))
      (node (ref "U4") (pin "41_3") (pinfunction "GND_41_3") (pintype "power_in"))
      (node (ref "U4") (pin "41_4") (pinfunction "GND_41_4") (pintype "power_in"))
      (node (ref "U4") (pin "41_5") (pinfunction "GND_41_5") (pintype "power_in"))
      (node (ref "U4") (pin "41_6") (pinfunction "GND_41_6") (pintype "power_in"))
      (node (ref "U4") (pin "41_7") (pinfunction "GND_41_7") (pintype "power_in"))
      (node (ref "U4") (pin "41_8") (pinfunction "GND_41_8") (pintype "power_in"))
      (node (ref "U4") (pin "41_9") (pinfunction "GND_41_9") (pintype "power_in"))
      (node (ref "U5") (pin "5") (pinfunction "GND_5") (pintype "passive"))
      (node (ref "U5") (pin "7") (pinfunction "EP_7") (pintype "passive"))
      (node (ref "U6") (pin "5") (pinfunction "GND_5") (pintype "passive"))
      (node (ref "U6") (pin "7") (pinfunction "EP_7") (pintype "passive"))
      (node (ref "U7") (pin "11") (pinfunction "TEST_11") (pintype "input"))
      (node (ref "U7") (pin "37") (pinfunction "EP_37") (pintype "power_in"))
      (node (ref "X1") (pin "2") (pinfunction "GND_2") (pintype "passive"))
      (node (ref "X1") (pin "4") (pinfunction "GND_4") (pintype "passive"))
    )
    (net (code "71") (name "Net-(D6-PadA)") (class "Default")
      (node (ref "D6") (pin "A") (pinfunction "A_A") (pintype "passive"))
      (node (ref "R43") (pin "1") (pinfunction "1_1") (pintype "passive"))
    )
    (net (code "72") (name "Net-(D7-PadA)") (class "Default")
      (node (ref "D7") (pin "A") (pinfunction "A_A") (pintype "passive"))
      (node (ref "R44") (pin "1") (pinfunction "1_1") (pintype "passive"))
    )
    (net (code "73") (name "Net-(D8-PadA)") (class "Default")
      (node (ref "D8") (pin "A") (pinfunction "A_A") (pintype "passive"))
      (node (ref "R45") (pin "1") (pinfunction "1_1") (pintype "passive"))
    )
    (net (code "74") (name "Net-(D9-PadA)") (class "Default")
      (node (ref "D9") (pin "A") (pinfunction "A_A") (pintype "passive"))
      (node (ref "R46") (pin "1") (pinfunction "1_1") (pintype "passive"))
    )
    (net (code "75") (name "Net-(D10-PadA)") (class "Default")
      (node (ref "D10") (pin "A") (pinfunction "A_A") (pintype "passive"))
      (node (ref "R5") (pin "1") (pinfunction "1_1") (pintype "passive"))
    )
    (net (code "76") (name "Net-(J5-CC1)") (class "Default")
      (node (ref "J5") (pin "A5") (pinfunction "CC1_A5") (pintype "bidirectional"))
      (node (ref "R42") (pin "1") (pinfunction "1_1") (pintype "passive"))
    )
    (net (code "77") (name "Net-(J5-CC2)") (class "Default")
      (node (ref "J5") (pin "B5") (pinfunction "CC2_B5") (pintype "bidirectional"))
      (node (ref "R41") (pin "1") (pinfunction "1_1") (pintype "passive"))
    )
    (net (code "78") (name "Net-(Q1-G)") (class "Default")
      (node (ref "Q1") (pin "4") (pinfunction "G_4") (pintype "passive"))
      (node (ref "R1") (pin "1") (pinfunction "1_1") (pintype "passive"))
      (node (ref "R7") (pin "2") (pinfunction "2_2") (pintype "passive"))
    )
    (net (code "79") (name "Net-(Q2-G)") (class "Default")
      (node (ref "Q2") (pin "4") (pinfunction "G_4") (pintype "passive"))
      (node (ref "R15") (pin "1") (pinfunction "1_1") (pintype "passive"))
      (node (ref "R17") (pin "2") (pinfunction "2_2") (pintype "passive"))
    )
    (net (code "80") (name "Net-(Q3-B)") (class "Default")
      (node (ref "Q3") (pin "1") (pinfunction "B_1") (pintype "passive"))
      (node (ref "R16") (pin "1") (pinfunction "1_1") (pintype "passive"))
    )
    (net (code "81") (name "Net-(Q3-C)") (class "Default")
      (node (ref "Q3") (pin "3") (pinfunction "C_3") (pintype "passive"))
      (node (ref "R14") (pin "1") (pinfunction "1_1") (pintype "passive"))
    )
    (net (code "82") (name "Net-(Q4-B)") (class "Default")
      (node (ref "Q4") (pin "1") (pinfunction "B_1") (pintype "passive"))
      (node (ref "R18") (pin "1") (pinfunction "1_1") (pintype "passive"))
    )
    (net (code "83") (name "Net-(Q4-C)") (class "Default")
      (node (ref "Q4") (pin "3") (pinfunction "C_3") (pintype "passive"))
      (node (ref "R19") (pin "1") (pinfunction "1_1") (pintype "passive"))
    )
    (net (code "84") (name "SH1_GND") (class "Default")
      (node (ref "C33") (pin "1") (pinfunction "1_1") (pintype "passive"))
      (node (ref "J1") (pin "SH1") (pinfunction "SHIELD_SH1") (pintype "passive"))
      (node (ref "J1") (pin "SH2") (pinfunction "SHIELD_SH2") (pintype "passive"))
      (node (ref "J1") (pin "SH3") (pinfunction "SHIELD_SH3") (pintype "passive"))
      (node (ref "J1") (pin "SH4") (pinfunction "SHIELD_SH4") (pintype "passive"))
    )
    (net (code "85") (name "SH2_GND") (class "Default")
      (node (ref "C35") (pin "1") (pinfunction "1_1") (pintype "passive"))
      (node (ref "J3") (pin "5") (pinfunction "EH_5") (pintype "passive"))
    )
    (net (code "86") (name "SH3_GND") (class "Default")
      (node (ref "C45") (pin "2") (pinfunction "2_2") (pintype "passive"))
      (node (ref "J5") (pin "SH1") (pinfunction "SHIELD_SH1") (pintype "passive"))
      (node (ref "J5") (pin "SH2") (pinfunction "SHIELD_SH2") (pintype "passive"))
      (node (ref "J5") (pin "SH3") (pinfunction "SHIELD_SH3") (pintype "passive"))
      (node (ref "J5") (pin "SH4") (pinfunction "SHIELD_SH4") (pintype "passive"))
    )
    (net (code "87") (name "SH4_GND") (class "Default")
      (node (ref "C46") (pin "2") (pinfunction "2_2") (pintype "passive"))
      (node (ref "J6") (pin "5") (pinfunction "SHIELD_5") (pintype "passive"))
      (node (ref "J6") (pin "6") (pinfunction "SHIELD_6") (pintype "passive"))
    )
    (net (code "88") (name "SH12_GND") (class "Default")
      (node (ref "C38") (pin "2") (pinfunction "2_2") (pintype "passive"))
      (node (ref "J4") (pin "5") (pinfunction "SHIELD_5") (pintype "passive"))
      (node (ref "J4") (pin "6") (pinfunction "SHIELD_6") (pintype "passive"))
    )
    (net (code "89") (name "unconnected-(J1-CC1-PadA5)") (class "Default")
      (node (ref "J1") (pin "A5") (pinfunction "CC1_A5") (pintype "bidirectional+no_connect"))
    )
    (net (code "90") (name "unconnected-(J1-CC2-PadB5)") (class "Default")
      (node (ref "J1") (pin "B5") (pinfunction "CC2_B5") (pintype "bidirectional+no_connect"))
    )
    (net (code "91") (name "unconnected-(J1-D1+-PadA6)") (class "Default")
      (node (ref "J1") (pin "A6") (pinfunction "D1+_A6") (pintype "bidirectional+no_connect"))
    )
    (net (code "92") (name "unconnected-(J1-D1--PadA7)") (class "Default")
      (node (ref "J1") (pin "A7") (pinfunction "D1-_A7") (pintype "bidirectional+no_connect"))
    )
    (net (code "93") (name "unconnected-(J1-D2+-PadB6)") (class "Default")
      (node (ref "J1") (pin "B6") (pinfunction "D2+_B6") (pintype "bidirectional+no_connect"))
    )
    (net (code "94") (name "unconnected-(J1-D2--PadB7)") (class "Default")
      (node (ref "J1") (pin "B7") (pinfunction "D2-_B7") (pintype "bidirectional+no_connect"))
    )
    (net (code "95") (name "unconnected-(J1-SBU1-PadA8)") (class "Default")
      (node (ref "J1") (pin "A8") (pinfunction "SBU1_A8") (pintype "bidirectional+no_connect"))
    )
    (net (code "96") (name "unconnected-(J1-SBU2-PadB8)") (class "Default")
      (node (ref "J1") (pin "B8") (pinfunction "SBU2_B8") (pintype "bidirectional+no_connect"))
    )
    (net (code "97") (name "unconnected-(J5-SBU1-PadA8)") (class "Default")
      (node (ref "J5") (pin "A8") (pinfunction "SBU1_A8") (pintype "bidirectional+no_connect"))
    )
    (net (code "98") (name "unconnected-(J5-SBU2-PadB8)") (class "Default")
      (node (ref "J5") (pin "B8") (pinfunction "SBU2_B8") (pintype "bidirectional+no_connect"))
    )
    (net (code "99") (name "unconnected-(U4-IO1-Pad39)") (class "Default")
      (node (ref "U4") (pin "39") (pinfunction "IO1_39") (pintype "passive+no_connect"))
    )
    (net (code "100") (name "unconnected-(U4-IO2-Pad38)") (class "Default")
      (node (ref "U4") (pin "38") (pinfunction "IO2_38") (pintype "passive+no_connect"))
    )
    (net (code "101") (name "unconnected-(U4-IO3-Pad15)") (class "Default")
      (node (ref "U4") (pin "15") (pinfunction "IO3_15") (pintype "passive+no_connect"))
    )
    (net (code "102") (name "unconnected-(U4-IO4-Pad4)") (class "Default")
      (node (ref "U4") (pin "4") (pinfunction "IO4_4") (pintype "passive+no_connect"))
    )
    (net (code "103") (name "unconnected-(U4-IO5-Pad5)") (class "Default")
      (node (ref "U4") (pin "5") (pinfunction "IO5_5") (pintype "passive+no_connect"))
    )
    (net (code "104") (name "unconnected-(U4-IO6-Pad6)") (class "Default")
      (node (ref "U4") (pin "6") (pinfunction "IO6_6") (pintype "passive+no_connect"))
    )
    (net (code "105") (name "unconnected-(U4-IO7-Pad7)") (class "Default")
      (node (ref "U4") (pin "7") (pinfunction "IO7_7") (pintype "passive+no_connect"))
    )
    (net (code "106") (name "unconnected-(U4-IO10-Pad18)") (class "Default")
      (node (ref "U4") (pin "18") (pinfunction "IO10_18") (pintype "passive+no_connect"))
    )
    (net (code "107") (name "unconnected-(U4-IO11-Pad19)") (class "Default")
      (node (ref "U4") (pin "19") (pinfunction "IO11_19") (pintype "passive+no_connect"))
    )
    (net (code "108") (name "unconnected-(U4-IO12-Pad20)") (class "Default")
      (node (ref "U4") (pin "20") (pinfunction "IO12_20") (pintype "passive+no_connect"))
    )
    (net (code "109") (name "unconnected-(U4-IO13-Pad21)") (class "Default")
      (node (ref "U4") (pin "21") (pinfunction "IO13_21") (pintype "passive+no_connect"))
    )
    (net (code "110") (name "unconnected-(U4-IO14-Pad22)") (class "Default")
      (node (ref "U4") (pin "22") (pinfunction "IO14_22") (pintype "passive+no_connect"))
    )
    (net (code "111") (name "unconnected-(U4-IO17-Pad10)") (class "Default")
      (node (ref "U4") (pin "10") (pinfunction "IO17_10") (pintype "passive+no_connect"))
    )
    (net (code "112") (name "unconnected-(U4-IO18-Pad11)") (class "Default")
      (node (ref "U4") (pin "11") (pinfunction "IO18_11") (pintype "passive+no_connect"))
    )
    (net (code "113") (name "unconnected-(U4-IO21-Pad23)") (class "Default")
      (node (ref "U4") (pin "23") (pinfunction "IO21_23") (pintype "passive+no_connect"))
    )
    (net (code "114") (name "unconnected-(U4-IO35-Pad28)") (class "Default")
      (node (ref "U4") (pin "28") (pinfunction "IO35_28") (pintype "passive+no_connect"))
    )
    (net (code "115") (name "unconnected-(U4-IO36-Pad29)") (class "Default")
      (node (ref "U4") (pin "29") (pinfunction "IO36_29") (pintype "passive+no_connect"))
    )
    (net (code "116") (name "unconnected-(U4-IO37-Pad30)") (class "Default")
      (node (ref "U4") (pin "30") (pinfunction "IO37_30") (pintype "passive+no_connect"))
    )
    (net (code "117") (name "unconnected-(U4-IO38-Pad31)") (class "Default")
      (node (ref "U4") (pin "31") (pinfunction "IO38_31") (pintype "passive+no_connect"))
    )
    (net (code "118") (name "unconnected-(U4-IO39-Pad32)") (class "Default")
      (node (ref "U4") (pin "32") (pinfunction "IO39_32") (pintype "passive+no_connect"))
    )
    (net (code "119") (name "unconnected-(U4-IO40-Pad33)") (class "Default")
      (node (ref "U4") (pin "33") (pinfunction "IO40_33") (pintype "passive+no_connect"))
    )
    (net (code "120") (name "unconnected-(U4-IO41-Pad34)") (class "Default")
      (node (ref "U4") (pin "34") (pinfunction "IO41_34") (pintype "passive+no_connect"))
    )
    (net (code "121") (name "unconnected-(U4-IO42-Pad35)") (class "Default")
      (node (ref "U4") (pin "35") (pinfunction "IO42_35") (pintype "passive+no_connect"))
    )
    (net (code "122") (name "unconnected-(U4-IO45-Pad26)") (class "Default")
      (node (ref "U4") (pin "26") (pinfunction "IO45_26") (pintype "passive+no_connect"))
    )
    (net (code "123") (name "unconnected-(U4-IO46-Pad16)") (class "Default")
      (node (ref "U4") (pin "16") (pinfunction "IO46_16") (pintype "passive+no_connect"))
    )
    (net (code "124") (name "unconnected-(U4-IO47-Pad24)") (class "Default")
      (node (ref "U4") (pin "24") (pinfunction "IO47_24") (pintype "passive+no_connect"))
    )
    (net (code "125") (name "unconnected-(U4-IO48-Pad25)") (class "Default")
      (node (ref "U4") (pin "25") (pinfunction "IO48_25") (pintype "passive+no_connect"))
    )
  )
)
